# AddSub.net
KiCad netlist of a schematic drawn in EAGLE
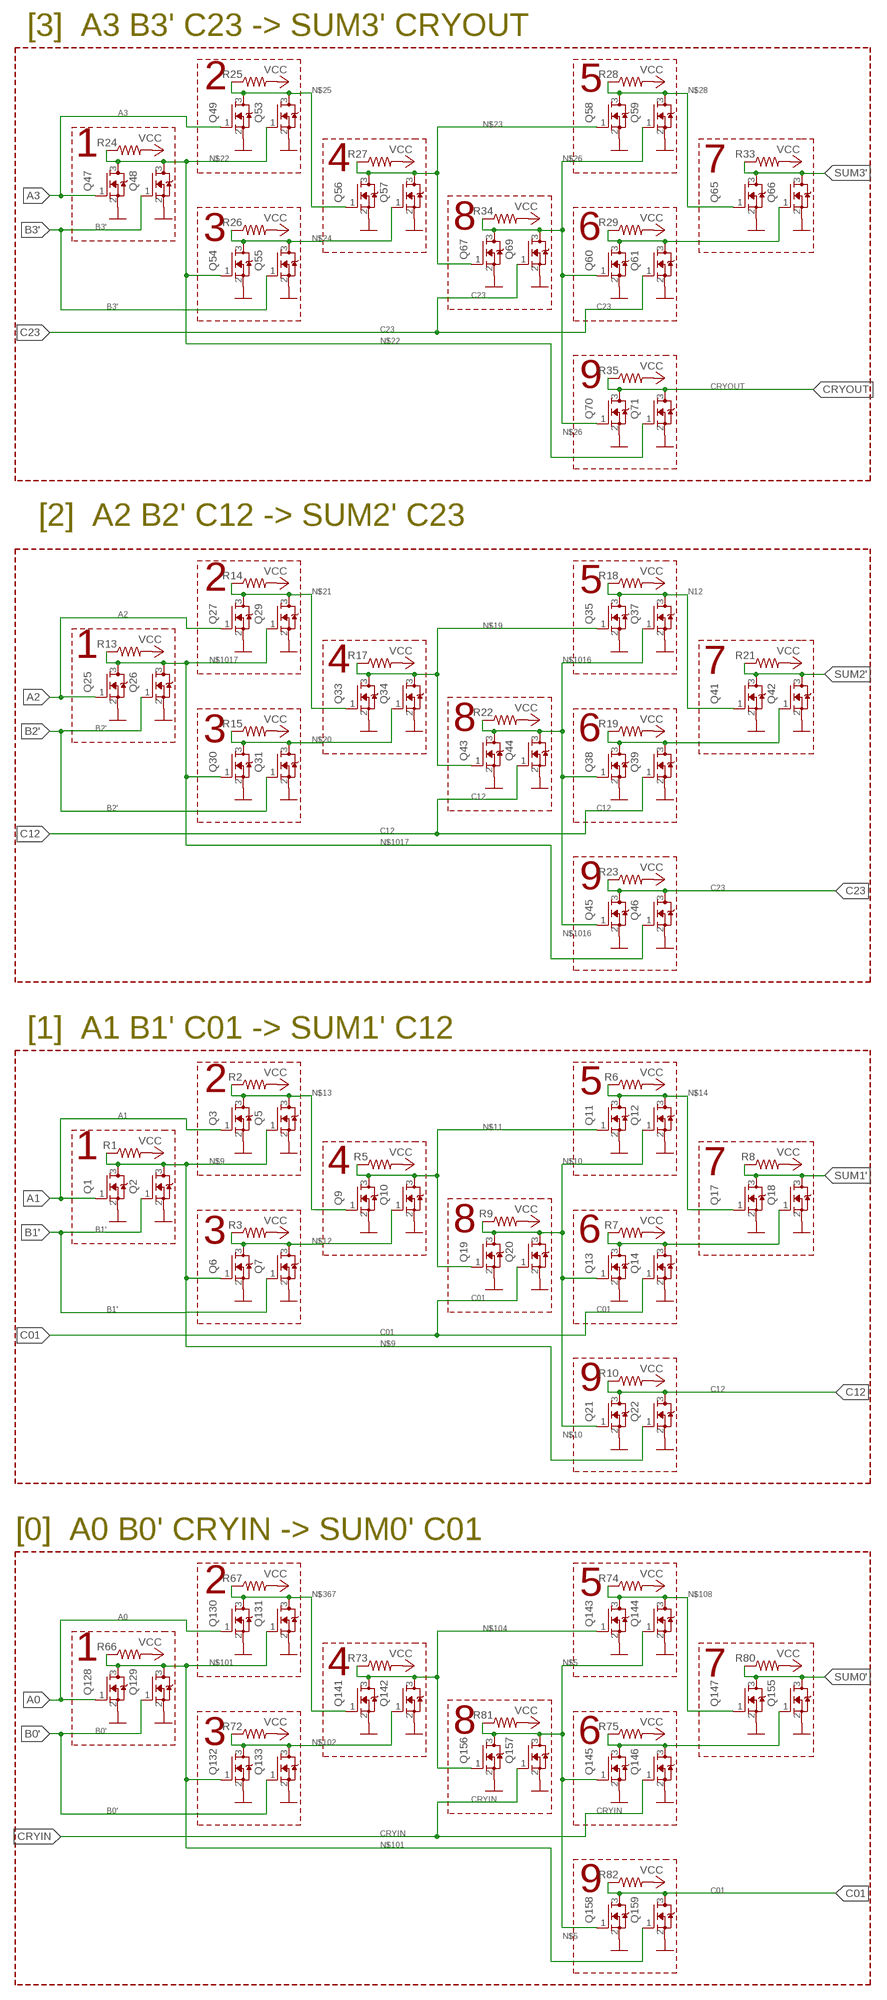
[diagram p0: schematic, sheet 1, part 1 of 2]
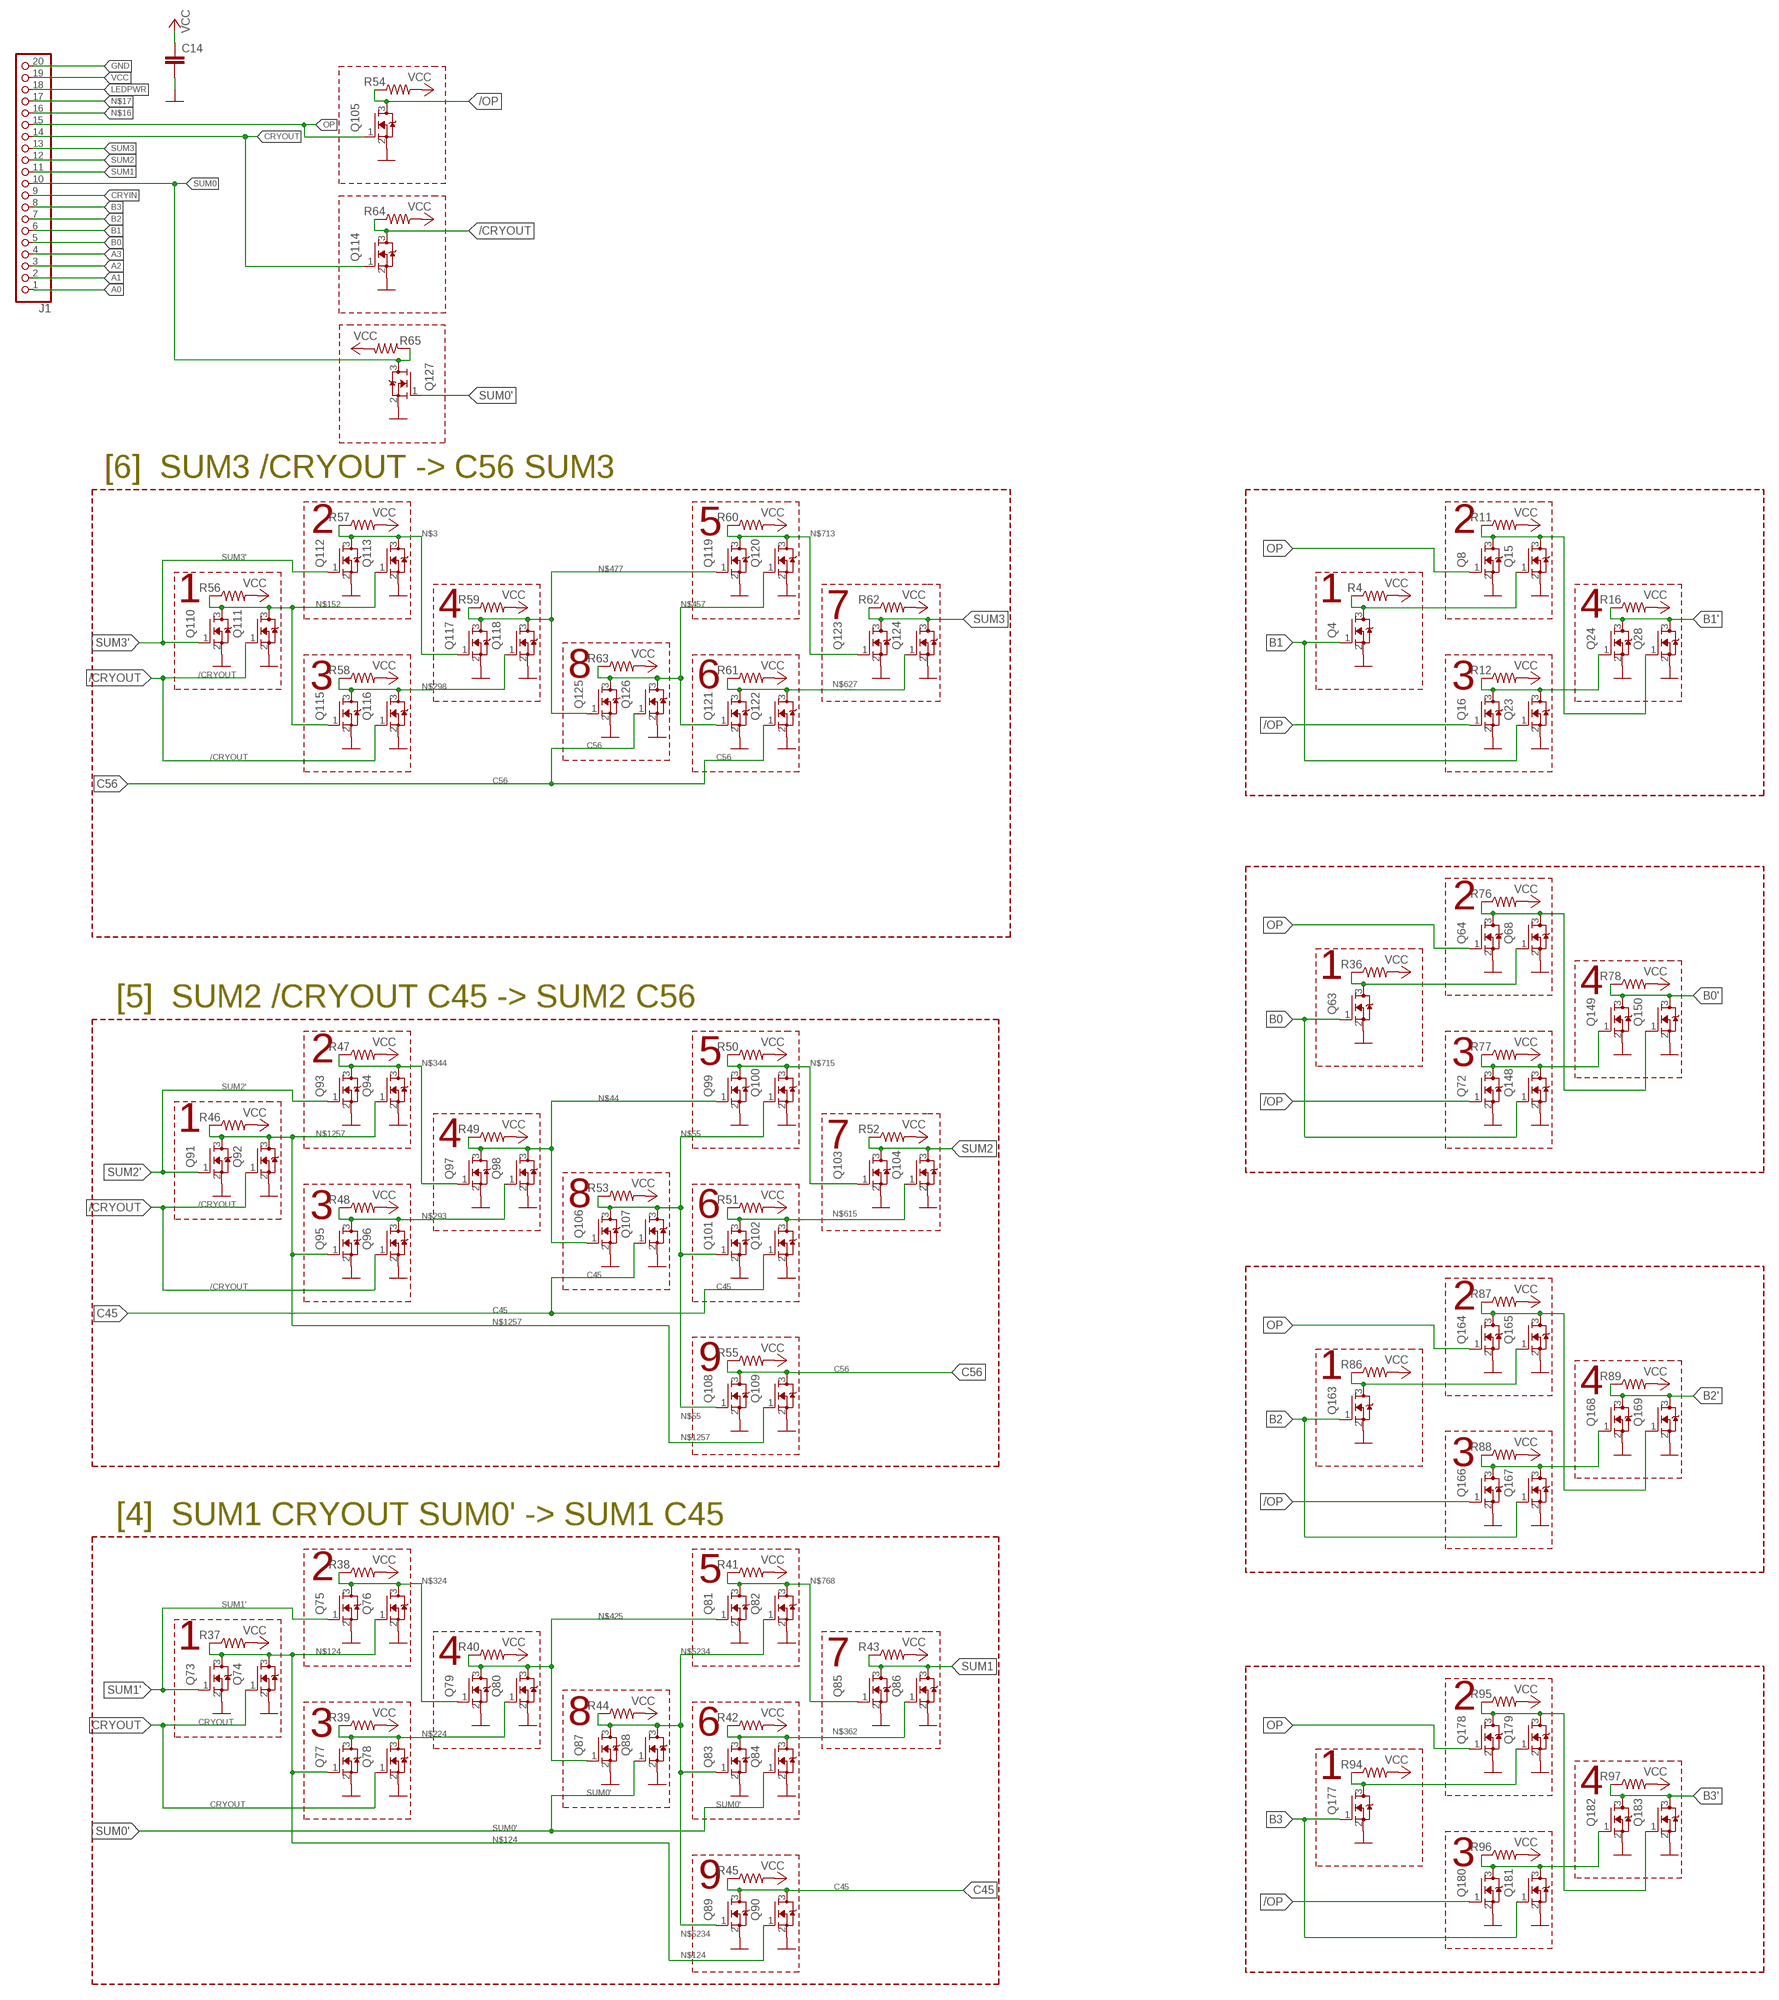
[diagram p1: schematic, sheet 1, part 2 of 2]

(export (version "E")
  (design (tool "Eeschema 10.0.6"))
  (components
    (comp (ref "C14")
      (value "C-EUC0805")
      (footprint "eagle-import:C0805")
      (libsource (lib "eagle-import") (part "C-EUC0805"))
    )
    (comp (ref "J1")
      (value "PINHD-1X20/90")
      (footprint "eagle-import:1X20_90")
      (libsource (lib "eagle-import") (part "PINHD-1X20/90"))
    )
    (comp (ref "Q1")
      (value "310mA/60V/1.6Ω")
      (footprint "eagle-import:SOT23")
      (libsource (lib "eagle-import") (part "NMOSREFLOW"))
    )
    (comp (ref "Q2")
      (value "310mA/60V/1.6Ω")
      (footprint "eagle-import:SOT23")
      (libsource (lib "eagle-import") (part "NMOSREFLOW"))
    )
    (comp (ref "Q3")
      (value "310mA/60V/1.6Ω")
      (footprint "eagle-import:SOT23")
      (libsource (lib "eagle-import") (part "NMOSREFLOW"))
    )
    (comp (ref "Q4")
      (value "310mA/60V/1.6Ω")
      (footprint "eagle-import:SOT23")
      (libsource (lib "eagle-import") (part "NMOSREFLOW"))
    )
    (comp (ref "Q5")
      (value "310mA/60V/1.6Ω")
      (footprint "eagle-import:SOT23")
      (libsource (lib "eagle-import") (part "NMOSREFLOW"))
    )
    (comp (ref "Q6")
      (value "310mA/60V/1.6Ω")
      (footprint "eagle-import:SOT23")
      (libsource (lib "eagle-import") (part "NMOSREFLOW"))
    )
    (comp (ref "Q7")
      (value "310mA/60V/1.6Ω")
      (footprint "eagle-import:SOT23")
      (libsource (lib "eagle-import") (part "NMOSREFLOW"))
    )
    (comp (ref "Q8")
      (value "310mA/60V/1.6Ω")
      (footprint "eagle-import:SOT23")
      (libsource (lib "eagle-import") (part "NMOSREFLOW"))
    )
    (comp (ref "Q9")
      (value "310mA/60V/1.6Ω")
      (footprint "eagle-import:SOT23")
      (libsource (lib "eagle-import") (part "NMOSREFLOW"))
    )
    (comp (ref "Q10")
      (value "310mA/60V/1.6Ω")
      (footprint "eagle-import:SOT23")
      (libsource (lib "eagle-import") (part "NMOSREFLOW"))
    )
    (comp (ref "Q11")
      (value "310mA/60V/1.6Ω")
      (footprint "eagle-import:SOT23")
      (libsource (lib "eagle-import") (part "NMOSREFLOW"))
    )
    (comp (ref "Q12")
      (value "310mA/60V/1.6Ω")
      (footprint "eagle-import:SOT23")
      (libsource (lib "eagle-import") (part "NMOSREFLOW"))
    )
    (comp (ref "Q13")
      (value "310mA/60V/1.6Ω")
      (footprint "eagle-import:SOT23")
      (libsource (lib "eagle-import") (part "NMOSREFLOW"))
    )
    (comp (ref "Q14")
      (value "310mA/60V/1.6Ω")
      (footprint "eagle-import:SOT23")
      (libsource (lib "eagle-import") (part "NMOSREFLOW"))
    )
    (comp (ref "Q15")
      (value "310mA/60V/1.6Ω")
      (footprint "eagle-import:SOT23")
      (libsource (lib "eagle-import") (part "NMOSREFLOW"))
    )
    (comp (ref "Q16")
      (value "310mA/60V/1.6Ω")
      (footprint "eagle-import:SOT23")
      (libsource (lib "eagle-import") (part "NMOSREFLOW"))
    )
    (comp (ref "Q17")
      (value "310mA/60V/1.6Ω")
      (footprint "eagle-import:SOT23")
      (libsource (lib "eagle-import") (part "NMOSREFLOW"))
    )
    (comp (ref "Q18")
      (value "310mA/60V/1.6Ω")
      (footprint "eagle-import:SOT23")
      (libsource (lib "eagle-import") (part "NMOSREFLOW"))
    )
    (comp (ref "Q19")
      (value "310mA/60V/1.6Ω")
      (footprint "eagle-import:SOT23")
      (libsource (lib "eagle-import") (part "NMOSREFLOW"))
    )
    (comp (ref "Q20")
      (value "310mA/60V/1.6Ω")
      (footprint "eagle-import:SOT23")
      (libsource (lib "eagle-import") (part "NMOSREFLOW"))
    )
    (comp (ref "Q21")
      (value "310mA/60V/1.6Ω")
      (footprint "eagle-import:SOT23")
      (libsource (lib "eagle-import") (part "NMOSREFLOW"))
    )
    (comp (ref "Q22")
      (value "310mA/60V/1.6Ω")
      (footprint "eagle-import:SOT23")
      (libsource (lib "eagle-import") (part "NMOSREFLOW"))
    )
    (comp (ref "Q23")
      (value "310mA/60V/1.6Ω")
      (footprint "eagle-import:SOT23")
      (libsource (lib "eagle-import") (part "NMOSREFLOW"))
    )
    (comp (ref "Q24")
      (value "310mA/60V/1.6Ω")
      (footprint "eagle-import:SOT23")
      (libsource (lib "eagle-import") (part "NMOSREFLOW"))
    )
    (comp (ref "Q25")
      (value "310mA/60V/1.6Ω")
      (footprint "eagle-import:SOT23")
      (libsource (lib "eagle-import") (part "NMOSREFLOW"))
    )
    (comp (ref "Q26")
      (value "310mA/60V/1.6Ω")
      (footprint "eagle-import:SOT23")
      (libsource (lib "eagle-import") (part "NMOSREFLOW"))
    )
    (comp (ref "Q27")
      (value "310mA/60V/1.6Ω")
      (footprint "eagle-import:SOT23")
      (libsource (lib "eagle-import") (part "NMOSREFLOW"))
    )
    (comp (ref "Q28")
      (value "310mA/60V/1.6Ω")
      (footprint "eagle-import:SOT23")
      (libsource (lib "eagle-import") (part "NMOSREFLOW"))
    )
    (comp (ref "Q29")
      (value "310mA/60V/1.6Ω")
      (footprint "eagle-import:SOT23")
      (libsource (lib "eagle-import") (part "NMOSREFLOW"))
    )
    (comp (ref "Q30")
      (value "310mA/60V/1.6Ω")
      (footprint "eagle-import:SOT23")
      (libsource (lib "eagle-import") (part "NMOSREFLOW"))
    )
    (comp (ref "Q31")
      (value "310mA/60V/1.6Ω")
      (footprint "eagle-import:SOT23")
      (libsource (lib "eagle-import") (part "NMOSREFLOW"))
    )
    (comp (ref "Q33")
      (value "310mA/60V/1.6Ω")
      (footprint "eagle-import:SOT23")
      (libsource (lib "eagle-import") (part "NMOSREFLOW"))
    )
    (comp (ref "Q34")
      (value "310mA/60V/1.6Ω")
      (footprint "eagle-import:SOT23")
      (libsource (lib "eagle-import") (part "NMOSREFLOW"))
    )
    (comp (ref "Q35")
      (value "310mA/60V/1.6Ω")
      (footprint "eagle-import:SOT23")
      (libsource (lib "eagle-import") (part "NMOSREFLOW"))
    )
    (comp (ref "Q37")
      (value "310mA/60V/1.6Ω")
      (footprint "eagle-import:SOT23")
      (libsource (lib "eagle-import") (part "NMOSREFLOW"))
    )
    (comp (ref "Q38")
      (value "310mA/60V/1.6Ω")
      (footprint "eagle-import:SOT23")
      (libsource (lib "eagle-import") (part "NMOSREFLOW"))
    )
    (comp (ref "Q39")
      (value "310mA/60V/1.6Ω")
      (footprint "eagle-import:SOT23")
      (libsource (lib "eagle-import") (part "NMOSREFLOW"))
    )
    (comp (ref "Q41")
      (value "310mA/60V/1.6Ω")
      (footprint "eagle-import:SOT23")
      (libsource (lib "eagle-import") (part "NMOSREFLOW"))
    )
    (comp (ref "Q42")
      (value "310mA/60V/1.6Ω")
      (footprint "eagle-import:SOT23")
      (libsource (lib "eagle-import") (part "NMOSREFLOW"))
    )
    (comp (ref "Q43")
      (value "310mA/60V/1.6Ω")
      (footprint "eagle-import:SOT23")
      (libsource (lib "eagle-import") (part "NMOSREFLOW"))
    )
    (comp (ref "Q44")
      (value "310mA/60V/1.6Ω")
      (footprint "eagle-import:SOT23")
      (libsource (lib "eagle-import") (part "NMOSREFLOW"))
    )
    (comp (ref "Q45")
      (value "310mA/60V/1.6Ω")
      (footprint "eagle-import:SOT23")
      (libsource (lib "eagle-import") (part "NMOSREFLOW"))
    )
    (comp (ref "Q46")
      (value "310mA/60V/1.6Ω")
      (footprint "eagle-import:SOT23")
      (libsource (lib "eagle-import") (part "NMOSREFLOW"))
    )
    (comp (ref "Q47")
      (value "310mA/60V/1.6Ω")
      (footprint "eagle-import:SOT23")
      (libsource (lib "eagle-import") (part "NMOSREFLOW"))
    )
    (comp (ref "Q48")
      (value "310mA/60V/1.6Ω")
      (footprint "eagle-import:SOT23")
      (libsource (lib "eagle-import") (part "NMOSREFLOW"))
    )
    (comp (ref "Q49")
      (value "310mA/60V/1.6Ω")
      (footprint "eagle-import:SOT23")
      (libsource (lib "eagle-import") (part "NMOSREFLOW"))
    )
    (comp (ref "Q53")
      (value "310mA/60V/1.6Ω")
      (footprint "eagle-import:SOT23")
      (libsource (lib "eagle-import") (part "NMOSREFLOW"))
    )
    (comp (ref "Q54")
      (value "310mA/60V/1.6Ω")
      (footprint "eagle-import:SOT23")
      (libsource (lib "eagle-import") (part "NMOSREFLOW"))
    )
    (comp (ref "Q55")
      (value "310mA/60V/1.6Ω")
      (footprint "eagle-import:SOT23")
      (libsource (lib "eagle-import") (part "NMOSREFLOW"))
    )
    (comp (ref "Q56")
      (value "310mA/60V/1.6Ω")
      (footprint "eagle-import:SOT23")
      (libsource (lib "eagle-import") (part "NMOSREFLOW"))
    )
    (comp (ref "Q57")
      (value "310mA/60V/1.6Ω")
      (footprint "eagle-import:SOT23")
      (libsource (lib "eagle-import") (part "NMOSREFLOW"))
    )
    (comp (ref "Q58")
      (value "310mA/60V/1.6Ω")
      (footprint "eagle-import:SOT23")
      (libsource (lib "eagle-import") (part "NMOSREFLOW"))
    )
    (comp (ref "Q59")
      (value "310mA/60V/1.6Ω")
      (footprint "eagle-import:SOT23")
      (libsource (lib "eagle-import") (part "NMOSREFLOW"))
    )
    (comp (ref "Q60")
      (value "310mA/60V/1.6Ω")
      (footprint "eagle-import:SOT23")
      (libsource (lib "eagle-import") (part "NMOSREFLOW"))
    )
    (comp (ref "Q61")
      (value "310mA/60V/1.6Ω")
      (footprint "eagle-import:SOT23")
      (libsource (lib "eagle-import") (part "NMOSREFLOW"))
    )
    (comp (ref "Q63")
      (value "310mA/60V/1.6Ω")
      (footprint "eagle-import:SOT23")
      (libsource (lib "eagle-import") (part "NMOSREFLOW"))
    )
    (comp (ref "Q64")
      (value "310mA/60V/1.6Ω")
      (footprint "eagle-import:SOT23")
      (libsource (lib "eagle-import") (part "NMOSREFLOW"))
    )
    (comp (ref "Q65")
      (value "310mA/60V/1.6Ω")
      (footprint "eagle-import:SOT23")
      (libsource (lib "eagle-import") (part "NMOSREFLOW"))
    )
    (comp (ref "Q66")
      (value "310mA/60V/1.6Ω")
      (footprint "eagle-import:SOT23")
      (libsource (lib "eagle-import") (part "NMOSREFLOW"))
    )
    (comp (ref "Q67")
      (value "310mA/60V/1.6Ω")
      (footprint "eagle-import:SOT23")
      (libsource (lib "eagle-import") (part "NMOSREFLOW"))
    )
    (comp (ref "Q68")
      (value "310mA/60V/1.6Ω")
      (footprint "eagle-import:SOT23")
      (libsource (lib "eagle-import") (part "NMOSREFLOW"))
    )
    (comp (ref "Q69")
      (value "310mA/60V/1.6Ω")
      (footprint "eagle-import:SOT23")
      (libsource (lib "eagle-import") (part "NMOSREFLOW"))
    )
    (comp (ref "Q70")
      (value "310mA/60V/1.6Ω")
      (footprint "eagle-import:SOT23")
      (libsource (lib "eagle-import") (part "NMOSREFLOW"))
    )
    (comp (ref "Q71")
      (value "310mA/60V/1.6Ω")
      (footprint "eagle-import:SOT23")
      (libsource (lib "eagle-import") (part "NMOSREFLOW"))
    )
    (comp (ref "Q72")
      (value "310mA/60V/1.6Ω")
      (footprint "eagle-import:SOT23")
      (libsource (lib "eagle-import") (part "NMOSREFLOW"))
    )
    (comp (ref "Q73")
      (value "310mA/60V/1.6Ω")
      (footprint "eagle-import:SOT23")
      (libsource (lib "eagle-import") (part "NMOSREFLOW"))
    )
    (comp (ref "Q74")
      (value "310mA/60V/1.6Ω")
      (footprint "eagle-import:SOT23")
      (libsource (lib "eagle-import") (part "NMOSREFLOW"))
    )
    (comp (ref "Q75")
      (value "310mA/60V/1.6Ω")
      (footprint "eagle-import:SOT23")
      (libsource (lib "eagle-import") (part "NMOSREFLOW"))
    )
    (comp (ref "Q76")
      (value "310mA/60V/1.6Ω")
      (footprint "eagle-import:SOT23")
      (libsource (lib "eagle-import") (part "NMOSREFLOW"))
    )
    (comp (ref "Q77")
      (value "310mA/60V/1.6Ω")
      (footprint "eagle-import:SOT23")
      (libsource (lib "eagle-import") (part "NMOSREFLOW"))
    )
    (comp (ref "Q78")
      (value "310mA/60V/1.6Ω")
      (footprint "eagle-import:SOT23")
      (libsource (lib "eagle-import") (part "NMOSREFLOW"))
    )
    (comp (ref "Q79")
      (value "310mA/60V/1.6Ω")
      (footprint "eagle-import:SOT23")
      (libsource (lib "eagle-import") (part "NMOSREFLOW"))
    )
    (comp (ref "Q80")
      (value "310mA/60V/1.6Ω")
      (footprint "eagle-import:SOT23")
      (libsource (lib "eagle-import") (part "NMOSREFLOW"))
    )
    (comp (ref "Q81")
      (value "310mA/60V/1.6Ω")
      (footprint "eagle-import:SOT23")
      (libsource (lib "eagle-import") (part "NMOSREFLOW"))
    )
    (comp (ref "Q82")
      (value "310mA/60V/1.6Ω")
      (footprint "eagle-import:SOT23")
      (libsource (lib "eagle-import") (part "NMOSREFLOW"))
    )
    (comp (ref "Q83")
      (value "310mA/60V/1.6Ω")
      (footprint "eagle-import:SOT23")
      (libsource (lib "eagle-import") (part "NMOSREFLOW"))
    )
    (comp (ref "Q84")
      (value "310mA/60V/1.6Ω")
      (footprint "eagle-import:SOT23")
      (libsource (lib "eagle-import") (part "NMOSREFLOW"))
    )
    (comp (ref "Q85")
      (value "310mA/60V/1.6Ω")
      (footprint "eagle-import:SOT23")
      (libsource (lib "eagle-import") (part "NMOSREFLOW"))
    )
    (comp (ref "Q86")
      (value "310mA/60V/1.6Ω")
      (footprint "eagle-import:SOT23")
      (libsource (lib "eagle-import") (part "NMOSREFLOW"))
    )
    (comp (ref "Q87")
      (value "310mA/60V/1.6Ω")
      (footprint "eagle-import:SOT23")
      (libsource (lib "eagle-import") (part "NMOSREFLOW"))
    )
    (comp (ref "Q88")
      (value "310mA/60V/1.6Ω")
      (footprint "eagle-import:SOT23")
      (libsource (lib "eagle-import") (part "NMOSREFLOW"))
    )
    (comp (ref "Q89")
      (value "310mA/60V/1.6Ω")
      (footprint "eagle-import:SOT23")
      (libsource (lib "eagle-import") (part "NMOSREFLOW"))
    )
    (comp (ref "Q90")
      (value "310mA/60V/1.6Ω")
      (footprint "eagle-import:SOT23")
      (libsource (lib "eagle-import") (part "NMOSREFLOW"))
    )
    (comp (ref "Q91")
      (value "310mA/60V/1.6Ω")
      (footprint "eagle-import:SOT23")
      (libsource (lib "eagle-import") (part "NMOSREFLOW"))
    )
    (comp (ref "Q92")
      (value "310mA/60V/1.6Ω")
      (footprint "eagle-import:SOT23")
      (libsource (lib "eagle-import") (part "NMOSREFLOW"))
    )
    (comp (ref "Q93")
      (value "310mA/60V/1.6Ω")
      (footprint "eagle-import:SOT23")
      (libsource (lib "eagle-import") (part "NMOSREFLOW"))
    )
    (comp (ref "Q94")
      (value "310mA/60V/1.6Ω")
      (footprint "eagle-import:SOT23")
      (libsource (lib "eagle-import") (part "NMOSREFLOW"))
    )
    (comp (ref "Q95")
      (value "310mA/60V/1.6Ω")
      (footprint "eagle-import:SOT23")
      (libsource (lib "eagle-import") (part "NMOSREFLOW"))
    )
    (comp (ref "Q96")
      (value "310mA/60V/1.6Ω")
      (footprint "eagle-import:SOT23")
      (libsource (lib "eagle-import") (part "NMOSREFLOW"))
    )
    (comp (ref "Q97")
      (value "310mA/60V/1.6Ω")
      (footprint "eagle-import:SOT23")
      (libsource (lib "eagle-import") (part "NMOSREFLOW"))
    )
    (comp (ref "Q98")
      (value "310mA/60V/1.6Ω")
      (footprint "eagle-import:SOT23")
      (libsource (lib "eagle-import") (part "NMOSREFLOW"))
    )
    (comp (ref "Q99")
      (value "310mA/60V/1.6Ω")
      (footprint "eagle-import:SOT23")
      (libsource (lib "eagle-import") (part "NMOSREFLOW"))
    )
    (comp (ref "Q100")
      (value "310mA/60V/1.6Ω")
      (footprint "eagle-import:SOT23")
      (libsource (lib "eagle-import") (part "NMOSREFLOW"))
    )
    (comp (ref "Q101")
      (value "310mA/60V/1.6Ω")
      (footprint "eagle-import:SOT23")
      (libsource (lib "eagle-import") (part "NMOSREFLOW"))
    )
    (comp (ref "Q102")
      (value "310mA/60V/1.6Ω")
      (footprint "eagle-import:SOT23")
      (libsource (lib "eagle-import") (part "NMOSREFLOW"))
    )
    (comp (ref "Q103")
      (value "310mA/60V/1.6Ω")
      (footprint "eagle-import:SOT23")
      (libsource (lib "eagle-import") (part "NMOSREFLOW"))
    )
    (comp (ref "Q104")
      (value "310mA/60V/1.6Ω")
      (footprint "eagle-import:SOT23")
      (libsource (lib "eagle-import") (part "NMOSREFLOW"))
    )
    (comp (ref "Q105")
      (value "310mA/60V/1.6Ω")
      (footprint "eagle-import:SOT23")
      (libsource (lib "eagle-import") (part "NMOSREFLOW"))
    )
    (comp (ref "Q106")
      (value "310mA/60V/1.6Ω")
      (footprint "eagle-import:SOT23")
      (libsource (lib "eagle-import") (part "NMOSREFLOW"))
    )
    (comp (ref "Q107")
      (value "310mA/60V/1.6Ω")
      (footprint "eagle-import:SOT23")
      (libsource (lib "eagle-import") (part "NMOSREFLOW"))
    )
    (comp (ref "Q108")
      (value "310mA/60V/1.6Ω")
      (footprint "eagle-import:SOT23")
      (libsource (lib "eagle-import") (part "NMOSREFLOW"))
    )
    (comp (ref "Q109")
      (value "310mA/60V/1.6Ω")
      (footprint "eagle-import:SOT23")
      (libsource (lib "eagle-import") (part "NMOSREFLOW"))
    )
    (comp (ref "Q110")
      (value "310mA/60V/1.6Ω")
      (footprint "eagle-import:SOT23")
      (libsource (lib "eagle-import") (part "NMOSREFLOW"))
    )
    (comp (ref "Q111")
      (value "310mA/60V/1.6Ω")
      (footprint "eagle-import:SOT23")
      (libsource (lib "eagle-import") (part "NMOSREFLOW"))
    )
    (comp (ref "Q112")
      (value "310mA/60V/1.6Ω")
      (footprint "eagle-import:SOT23")
      (libsource (lib "eagle-import") (part "NMOSREFLOW"))
    )
    (comp (ref "Q113")
      (value "310mA/60V/1.6Ω")
      (footprint "eagle-import:SOT23")
      (libsource (lib "eagle-import") (part "NMOSREFLOW"))
    )
    (comp (ref "Q114")
      (value "310mA/60V/1.6Ω")
      (footprint "eagle-import:SOT23")
      (libsource (lib "eagle-import") (part "NMOSREFLOW"))
    )
    (comp (ref "Q115")
      (value "310mA/60V/1.6Ω")
      (footprint "eagle-import:SOT23")
      (libsource (lib "eagle-import") (part "NMOSREFLOW"))
    )
    (comp (ref "Q116")
      (value "310mA/60V/1.6Ω")
      (footprint "eagle-import:SOT23")
      (libsource (lib "eagle-import") (part "NMOSREFLOW"))
    )
    (comp (ref "Q117")
      (value "310mA/60V/1.6Ω")
      (footprint "eagle-import:SOT23")
      (libsource (lib "eagle-import") (part "NMOSREFLOW"))
    )
    (comp (ref "Q118")
      (value "310mA/60V/1.6Ω")
      (footprint "eagle-import:SOT23")
      (libsource (lib "eagle-import") (part "NMOSREFLOW"))
    )
    (comp (ref "Q119")
      (value "310mA/60V/1.6Ω")
      (footprint "eagle-import:SOT23")
      (libsource (lib "eagle-import") (part "NMOSREFLOW"))
    )
    (comp (ref "Q120")
      (value "310mA/60V/1.6Ω")
      (footprint "eagle-import:SOT23")
      (libsource (lib "eagle-import") (part "NMOSREFLOW"))
    )
    (comp (ref "Q121")
      (value "310mA/60V/1.6Ω")
      (footprint "eagle-import:SOT23")
      (libsource (lib "eagle-import") (part "NMOSREFLOW"))
    )
    (comp (ref "Q122")
      (value "310mA/60V/1.6Ω")
      (footprint "eagle-import:SOT23")
      (libsource (lib "eagle-import") (part "NMOSREFLOW"))
    )
    (comp (ref "Q123")
      (value "310mA/60V/1.6Ω")
      (footprint "eagle-import:SOT23")
      (libsource (lib "eagle-import") (part "NMOSREFLOW"))
    )
    (comp (ref "Q124")
      (value "310mA/60V/1.6Ω")
      (footprint "eagle-import:SOT23")
      (libsource (lib "eagle-import") (part "NMOSREFLOW"))
    )
    (comp (ref "Q125")
      (value "310mA/60V/1.6Ω")
      (footprint "eagle-import:SOT23")
      (libsource (lib "eagle-import") (part "NMOSREFLOW"))
    )
    (comp (ref "Q126")
      (value "310mA/60V/1.6Ω")
      (footprint "eagle-import:SOT23")
      (libsource (lib "eagle-import") (part "NMOSREFLOW"))
    )
    (comp (ref "Q127")
      (value "310mA/60V/1.6Ω")
      (footprint "eagle-import:SOT23")
      (libsource (lib "eagle-import") (part "NMOSREFLOW"))
    )
    (comp (ref "Q128")
      (value "310mA/60V/1.6Ω")
      (footprint "eagle-import:SOT23")
      (libsource (lib "eagle-import") (part "NMOSREFLOW"))
    )
    (comp (ref "Q129")
      (value "310mA/60V/1.6Ω")
      (footprint "eagle-import:SOT23")
      (libsource (lib "eagle-import") (part "NMOSREFLOW"))
    )
    (comp (ref "Q130")
      (value "310mA/60V/1.6Ω")
      (footprint "eagle-import:SOT23")
      (libsource (lib "eagle-import") (part "NMOSREFLOW"))
    )
    (comp (ref "Q131")
      (value "310mA/60V/1.6Ω")
      (footprint "eagle-import:SOT23")
      (libsource (lib "eagle-import") (part "NMOSREFLOW"))
    )
    (comp (ref "Q132")
      (value "310mA/60V/1.6Ω")
      (footprint "eagle-import:SOT23")
      (libsource (lib "eagle-import") (part "NMOSREFLOW"))
    )
    (comp (ref "Q133")
      (value "310mA/60V/1.6Ω")
      (footprint "eagle-import:SOT23")
      (libsource (lib "eagle-import") (part "NMOSREFLOW"))
    )
    (comp (ref "Q141")
      (value "310mA/60V/1.6Ω")
      (footprint "eagle-import:SOT23")
      (libsource (lib "eagle-import") (part "NMOSREFLOW"))
    )
    (comp (ref "Q142")
      (value "310mA/60V/1.6Ω")
      (footprint "eagle-import:SOT23")
      (libsource (lib "eagle-import") (part "NMOSREFLOW"))
    )
    (comp (ref "Q143")
      (value "310mA/60V/1.6Ω")
      (footprint "eagle-import:SOT23")
      (libsource (lib "eagle-import") (part "NMOSREFLOW"))
    )
    (comp (ref "Q144")
      (value "310mA/60V/1.6Ω")
      (footprint "eagle-import:SOT23")
      (libsource (lib "eagle-import") (part "NMOSREFLOW"))
    )
    (comp (ref "Q145")
      (value "310mA/60V/1.6Ω")
      (footprint "eagle-import:SOT23")
      (libsource (lib "eagle-import") (part "NMOSREFLOW"))
    )
    (comp (ref "Q146")
      (value "310mA/60V/1.6Ω")
      (footprint "eagle-import:SOT23")
      (libsource (lib "eagle-import") (part "NMOSREFLOW"))
    )
    (comp (ref "Q147")
      (value "310mA/60V/1.6Ω")
      (footprint "eagle-import:SOT23")
      (libsource (lib "eagle-import") (part "NMOSREFLOW"))
    )
    (comp (ref "Q148")
      (value "310mA/60V/1.6Ω")
      (footprint "eagle-import:SOT23")
      (libsource (lib "eagle-import") (part "NMOSREFLOW"))
    )
    (comp (ref "Q149")
      (value "310mA/60V/1.6Ω")
      (footprint "eagle-import:SOT23")
      (libsource (lib "eagle-import") (part "NMOSREFLOW"))
    )
    (comp (ref "Q150")
      (value "310mA/60V/1.6Ω")
      (footprint "eagle-import:SOT23")
      (libsource (lib "eagle-import") (part "NMOSREFLOW"))
    )
    (comp (ref "Q155")
      (value "310mA/60V/1.6Ω")
      (footprint "eagle-import:SOT23")
      (libsource (lib "eagle-import") (part "NMOSREFLOW"))
    )
    (comp (ref "Q156")
      (value "310mA/60V/1.6Ω")
      (footprint "eagle-import:SOT23")
      (libsource (lib "eagle-import") (part "NMOSREFLOW"))
    )
    (comp (ref "Q157")
      (value "310mA/60V/1.6Ω")
      (footprint "eagle-import:SOT23")
      (libsource (lib "eagle-import") (part "NMOSREFLOW"))
    )
    (comp (ref "Q158")
      (value "310mA/60V/1.6Ω")
      (footprint "eagle-import:SOT23")
      (libsource (lib "eagle-import") (part "NMOSREFLOW"))
    )
    (comp (ref "Q159")
      (value "310mA/60V/1.6Ω")
      (footprint "eagle-import:SOT23")
      (libsource (lib "eagle-import") (part "NMOSREFLOW"))
    )
    (comp (ref "Q163")
      (value "310mA/60V/1.6Ω")
      (footprint "eagle-import:SOT23")
      (libsource (lib "eagle-import") (part "NMOSREFLOW"))
    )
    (comp (ref "Q164")
      (value "310mA/60V/1.6Ω")
      (footprint "eagle-import:SOT23")
      (libsource (lib "eagle-import") (part "NMOSREFLOW"))
    )
    (comp (ref "Q165")
      (value "310mA/60V/1.6Ω")
      (footprint "eagle-import:SOT23")
      (libsource (lib "eagle-import") (part "NMOSREFLOW"))
    )
    (comp (ref "Q166")
      (value "310mA/60V/1.6Ω")
      (footprint "eagle-import:SOT23")
      (libsource (lib "eagle-import") (part "NMOSREFLOW"))
    )
    (comp (ref "Q167")
      (value "310mA/60V/1.6Ω")
      (footprint "eagle-import:SOT23")
      (libsource (lib "eagle-import") (part "NMOSREFLOW"))
    )
    (comp (ref "Q168")
      (value "310mA/60V/1.6Ω")
      (footprint "eagle-import:SOT23")
      (libsource (lib "eagle-import") (part "NMOSREFLOW"))
    )
    (comp (ref "Q169")
      (value "310mA/60V/1.6Ω")
      (footprint "eagle-import:SOT23")
      (libsource (lib "eagle-import") (part "NMOSREFLOW"))
    )
    (comp (ref "Q177")
      (value "310mA/60V/1.6Ω")
      (footprint "eagle-import:SOT23")
      (libsource (lib "eagle-import") (part "NMOSREFLOW"))
    )
    (comp (ref "Q178")
      (value "310mA/60V/1.6Ω")
      (footprint "eagle-import:SOT23")
      (libsource (lib "eagle-import") (part "NMOSREFLOW"))
    )
    (comp (ref "Q179")
      (value "310mA/60V/1.6Ω")
      (footprint "eagle-import:SOT23")
      (libsource (lib "eagle-import") (part "NMOSREFLOW"))
    )
    (comp (ref "Q180")
      (value "310mA/60V/1.6Ω")
      (footprint "eagle-import:SOT23")
      (libsource (lib "eagle-import") (part "NMOSREFLOW"))
    )
    (comp (ref "Q181")
      (value "310mA/60V/1.6Ω")
      (footprint "eagle-import:SOT23")
      (libsource (lib "eagle-import") (part "NMOSREFLOW"))
    )
    (comp (ref "Q182")
      (value "310mA/60V/1.6Ω")
      (footprint "eagle-import:SOT23")
      (libsource (lib "eagle-import") (part "NMOSREFLOW"))
    )
    (comp (ref "Q183")
      (value "310mA/60V/1.6Ω")
      (footprint "eagle-import:SOT23")
      (libsource (lib "eagle-import") (part "NMOSREFLOW"))
    )
    (comp (ref "R1")
      (value "RESISTOR0805")
      (footprint "eagle-import:0805")
      (libsource (lib "eagle-import") (part "RESISTOR0805"))
    )
    (comp (ref "R2")
      (value "RESISTOR0805")
      (footprint "eagle-import:0805")
      (libsource (lib "eagle-import") (part "RESISTOR0805"))
    )
    (comp (ref "R3")
      (value "RESISTOR0805")
      (footprint "eagle-import:0805")
      (libsource (lib "eagle-import") (part "RESISTOR0805"))
    )
    (comp (ref "R4")
      (value "RESISTOR0805")
      (footprint "eagle-import:0805")
      (libsource (lib "eagle-import") (part "RESISTOR0805"))
    )
    (comp (ref "R5")
      (value "RESISTOR0805")
      (footprint "eagle-import:0805")
      (libsource (lib "eagle-import") (part "RESISTOR0805"))
    )
    (comp (ref "R6")
      (value "RESISTOR0805")
      (footprint "eagle-import:0805")
      (libsource (lib "eagle-import") (part "RESISTOR0805"))
    )
    (comp (ref "R7")
      (value "RESISTOR0805")
      (footprint "eagle-import:0805")
      (libsource (lib "eagle-import") (part "RESISTOR0805"))
    )
    (comp (ref "R8")
      (value "RESISTOR0805")
      (footprint "eagle-import:0805")
      (libsource (lib "eagle-import") (part "RESISTOR0805"))
    )
    (comp (ref "R9")
      (value "RESISTOR0805")
      (footprint "eagle-import:0805")
      (libsource (lib "eagle-import") (part "RESISTOR0805"))
    )
    (comp (ref "R10")
      (value "RESISTOR0805")
      (footprint "eagle-import:0805")
      (libsource (lib "eagle-import") (part "RESISTOR0805"))
    )
    (comp (ref "R11")
      (value "RESISTOR0805")
      (footprint "eagle-import:0805")
      (libsource (lib "eagle-import") (part "RESISTOR0805"))
    )
    (comp (ref "R12")
      (value "RESISTOR0805")
      (footprint "eagle-import:0805")
      (libsource (lib "eagle-import") (part "RESISTOR0805"))
    )
    (comp (ref "R13")
      (value "RESISTOR0805")
      (footprint "eagle-import:0805")
      (libsource (lib "eagle-import") (part "RESISTOR0805"))
    )
    (comp (ref "R14")
      (value "RESISTOR0805")
      (footprint "eagle-import:0805")
      (libsource (lib "eagle-import") (part "RESISTOR0805"))
    )
    (comp (ref "R15")
      (value "RESISTOR0805")
      (footprint "eagle-import:0805")
      (libsource (lib "eagle-import") (part "RESISTOR0805"))
    )
    (comp (ref "R16")
      (value "RESISTOR0805")
      (footprint "eagle-import:0805")
      (libsource (lib "eagle-import") (part "RESISTOR0805"))
    )
    (comp (ref "R17")
      (value "RESISTOR0805")
      (footprint "eagle-import:0805")
      (libsource (lib "eagle-import") (part "RESISTOR0805"))
    )
    (comp (ref "R18")
      (value "RESISTOR0805")
      (footprint "eagle-import:0805")
      (libsource (lib "eagle-import") (part "RESISTOR0805"))
    )
    (comp (ref "R19")
      (value "RESISTOR0805")
      (footprint "eagle-import:0805")
      (libsource (lib "eagle-import") (part "RESISTOR0805"))
    )
    (comp (ref "R21")
      (value "RESISTOR0805")
      (footprint "eagle-import:0805")
      (libsource (lib "eagle-import") (part "RESISTOR0805"))
    )
    (comp (ref "R22")
      (value "RESISTOR0805")
      (footprint "eagle-import:0805")
      (libsource (lib "eagle-import") (part "RESISTOR0805"))
    )
    (comp (ref "R23")
      (value "RESISTOR0805")
      (footprint "eagle-import:0805")
      (libsource (lib "eagle-import") (part "RESISTOR0805"))
    )
    (comp (ref "R24")
      (value "RESISTOR0805")
      (footprint "eagle-import:0805")
      (libsource (lib "eagle-import") (part "RESISTOR0805"))
    )
    (comp (ref "R25")
      (value "RESISTOR0805")
      (footprint "eagle-import:0805")
      (libsource (lib "eagle-import") (part "RESISTOR0805"))
    )
    (comp (ref "R26")
      (value "RESISTOR0805")
      (footprint "eagle-import:0805")
      (libsource (lib "eagle-import") (part "RESISTOR0805"))
    )
    (comp (ref "R27")
      (value "RESISTOR0805")
      (footprint "eagle-import:0805")
      (libsource (lib "eagle-import") (part "RESISTOR0805"))
    )
    (comp (ref "R28")
      (value "RESISTOR0805")
      (footprint "eagle-import:0805")
      (libsource (lib "eagle-import") (part "RESISTOR0805"))
    )
    (comp (ref "R29")
      (value "RESISTOR0805")
      (footprint "eagle-import:0805")
      (libsource (lib "eagle-import") (part "RESISTOR0805"))
    )
    (comp (ref "R33")
      (value "RESISTOR0805")
      (footprint "eagle-import:0805")
      (libsource (lib "eagle-import") (part "RESISTOR0805"))
    )
    (comp (ref "R34")
      (value "RESISTOR0805")
      (footprint "eagle-import:0805")
      (libsource (lib "eagle-import") (part "RESISTOR0805"))
    )
    (comp (ref "R35")
      (value "RESISTOR0805")
      (footprint "eagle-import:0805")
      (libsource (lib "eagle-import") (part "RESISTOR0805"))
    )
    (comp (ref "R36")
      (value "RESISTOR0805")
      (footprint "eagle-import:0805")
      (libsource (lib "eagle-import") (part "RESISTOR0805"))
    )
    (comp (ref "R37")
      (value "RESISTOR0805")
      (footprint "eagle-import:0805")
      (libsource (lib "eagle-import") (part "RESISTOR0805"))
    )
    (comp (ref "R38")
      (value "RESISTOR0805")
      (footprint "eagle-import:0805")
      (libsource (lib "eagle-import") (part "RESISTOR0805"))
    )
    (comp (ref "R39")
      (value "RESISTOR0805")
      (footprint "eagle-import:0805")
      (libsource (lib "eagle-import") (part "RESISTOR0805"))
    )
    (comp (ref "R40")
      (value "RESISTOR0805")
      (footprint "eagle-import:0805")
      (libsource (lib "eagle-import") (part "RESISTOR0805"))
    )
    (comp (ref "R41")
      (value "RESISTOR0805")
      (footprint "eagle-import:0805")
      (libsource (lib "eagle-import") (part "RESISTOR0805"))
    )
    (comp (ref "R42")
      (value "RESISTOR0805")
      (footprint "eagle-import:0805")
      (libsource (lib "eagle-import") (part "RESISTOR0805"))
    )
    (comp (ref "R43")
      (value "RESISTOR0805")
      (footprint "eagle-import:0805")
      (libsource (lib "eagle-import") (part "RESISTOR0805"))
    )
    (comp (ref "R44")
      (value "RESISTOR0805")
      (footprint "eagle-import:0805")
      (libsource (lib "eagle-import") (part "RESISTOR0805"))
    )
    (comp (ref "R45")
      (value "RESISTOR0805")
      (footprint "eagle-import:0805")
      (libsource (lib "eagle-import") (part "RESISTOR0805"))
    )
    (comp (ref "R46")
      (value "RESISTOR0805")
      (footprint "eagle-import:0805")
      (libsource (lib "eagle-import") (part "RESISTOR0805"))
    )
    (comp (ref "R47")
      (value "RESISTOR0805")
      (footprint "eagle-import:0805")
      (libsource (lib "eagle-import") (part "RESISTOR0805"))
    )
    (comp (ref "R48")
      (value "RESISTOR0805")
      (footprint "eagle-import:0805")
      (libsource (lib "eagle-import") (part "RESISTOR0805"))
    )
    (comp (ref "R49")
      (value "RESISTOR0805")
      (footprint "eagle-import:0805")
      (libsource (lib "eagle-import") (part "RESISTOR0805"))
    )
    (comp (ref "R50")
      (value "RESISTOR0805")
      (footprint "eagle-import:0805")
      (libsource (lib "eagle-import") (part "RESISTOR0805"))
    )
    (comp (ref "R51")
      (value "RESISTOR0805")
      (footprint "eagle-import:0805")
      (libsource (lib "eagle-import") (part "RESISTOR0805"))
    )
    (comp (ref "R52")
      (value "RESISTOR0805")
      (footprint "eagle-import:0805")
      (libsource (lib "eagle-import") (part "RESISTOR0805"))
    )
    (comp (ref "R53")
      (value "RESISTOR0805")
      (footprint "eagle-import:0805")
      (libsource (lib "eagle-import") (part "RESISTOR0805"))
    )
    (comp (ref "R54")
      (value "RESISTOR0805")
      (footprint "eagle-import:0805")
      (libsource (lib "eagle-import") (part "RESISTOR0805"))
    )
    (comp (ref "R55")
      (value "RESISTOR0805")
      (footprint "eagle-import:0805")
      (libsource (lib "eagle-import") (part "RESISTOR0805"))
    )
    (comp (ref "R56")
      (value "RESISTOR0805")
      (footprint "eagle-import:0805")
      (libsource (lib "eagle-import") (part "RESISTOR0805"))
    )
    (comp (ref "R57")
      (value "RESISTOR0805")
      (footprint "eagle-import:0805")
      (libsource (lib "eagle-import") (part "RESISTOR0805"))
    )
    (comp (ref "R58")
      (value "RESISTOR0805")
      (footprint "eagle-import:0805")
      (libsource (lib "eagle-import") (part "RESISTOR0805"))
    )
    (comp (ref "R59")
      (value "RESISTOR0805")
      (footprint "eagle-import:0805")
      (libsource (lib "eagle-import") (part "RESISTOR0805"))
    )
    (comp (ref "R60")
      (value "RESISTOR0805")
      (footprint "eagle-import:0805")
      (libsource (lib "eagle-import") (part "RESISTOR0805"))
    )
    (comp (ref "R61")
      (value "RESISTOR0805")
      (footprint "eagle-import:0805")
      (libsource (lib "eagle-import") (part "RESISTOR0805"))
    )
    (comp (ref "R62")
      (value "RESISTOR0805")
      (footprint "eagle-import:0805")
      (libsource (lib "eagle-import") (part "RESISTOR0805"))
    )
    (comp (ref "R63")
      (value "RESISTOR0805")
      (footprint "eagle-import:0805")
      (libsource (lib "eagle-import") (part "RESISTOR0805"))
    )
    (comp (ref "R64")
      (value "RESISTOR0805")
      (footprint "eagle-import:0805")
      (libsource (lib "eagle-import") (part "RESISTOR0805"))
    )
    (comp (ref "R65")
      (value "RESISTOR0805")
      (footprint "eagle-import:0805")
      (libsource (lib "eagle-import") (part "RESISTOR0805"))
    )
    (comp (ref "R66")
      (value "RESISTOR0805")
      (footprint "eagle-import:0805")
      (libsource (lib "eagle-import") (part "RESISTOR0805"))
    )
    (comp (ref "R67")
      (value "RESISTOR0805")
      (footprint "eagle-import:0805")
      (libsource (lib "eagle-import") (part "RESISTOR0805"))
    )
    (comp (ref "R72")
      (value "RESISTOR0805")
      (footprint "eagle-import:0805")
      (libsource (lib "eagle-import") (part "RESISTOR0805"))
    )
    (comp (ref "R73")
      (value "RESISTOR0805")
      (footprint "eagle-import:0805")
      (libsource (lib "eagle-import") (part "RESISTOR0805"))
    )
    (comp (ref "R74")
      (value "RESISTOR0805")
      (footprint "eagle-import:0805")
      (libsource (lib "eagle-import") (part "RESISTOR0805"))
    )
    (comp (ref "R75")
      (value "RESISTOR0805")
      (footprint "eagle-import:0805")
      (libsource (lib "eagle-import") (part "RESISTOR0805"))
    )
    (comp (ref "R76")
      (value "RESISTOR0805")
      (footprint "eagle-import:0805")
      (libsource (lib "eagle-import") (part "RESISTOR0805"))
    )
    (comp (ref "R77")
      (value "RESISTOR0805")
      (footprint "eagle-import:0805")
      (libsource (lib "eagle-import") (part "RESISTOR0805"))
    )
    (comp (ref "R78")
      (value "RESISTOR0805")
      (footprint "eagle-import:0805")
      (libsource (lib "eagle-import") (part "RESISTOR0805"))
    )
    (comp (ref "R80")
      (value "RESISTOR0805")
      (footprint "eagle-import:0805")
      (libsource (lib "eagle-import") (part "RESISTOR0805"))
    )
    (comp (ref "R81")
      (value "RESISTOR0805")
      (footprint "eagle-import:0805")
      (libsource (lib "eagle-import") (part "RESISTOR0805"))
    )
    (comp (ref "R82")
      (value "RESISTOR0805")
      (footprint "eagle-import:0805")
      (libsource (lib "eagle-import") (part "RESISTOR0805"))
    )
    (comp (ref "R86")
      (value "RESISTOR0805")
      (footprint "eagle-import:0805")
      (libsource (lib "eagle-import") (part "RESISTOR0805"))
    )
    (comp (ref "R87")
      (value "RESISTOR0805")
      (footprint "eagle-import:0805")
      (libsource (lib "eagle-import") (part "RESISTOR0805"))
    )
    (comp (ref "R88")
      (value "RESISTOR0805")
      (footprint "eagle-import:0805")
      (libsource (lib "eagle-import") (part "RESISTOR0805"))
    )
    (comp (ref "R89")
      (value "RESISTOR0805")
      (footprint "eagle-import:0805")
      (libsource (lib "eagle-import") (part "RESISTOR0805"))
    )
    (comp (ref "R94")
      (value "RESISTOR0805")
      (footprint "eagle-import:0805")
      (libsource (lib "eagle-import") (part "RESISTOR0805"))
    )
    (comp (ref "R95")
      (value "RESISTOR0805")
      (footprint "eagle-import:0805")
      (libsource (lib "eagle-import") (part "RESISTOR0805"))
    )
    (comp (ref "R96")
      (value "RESISTOR0805")
      (footprint "eagle-import:0805")
      (libsource (lib "eagle-import") (part "RESISTOR0805"))
    )
    (comp (ref "R97")
      (value "RESISTOR0805")
      (footprint "eagle-import:0805")
      (libsource (lib "eagle-import") (part "RESISTOR0805"))
    )
  )
  (nets
    (net (code "1") (name "/N$3") (class "Default")
      (node (ref "Q112") (pin "3") (pinfunction "D_3") (pintype "bidirectional"))
      (node (ref "Q113") (pin "3") (pinfunction "D_3") (pintype "bidirectional"))
      (node (ref "Q117") (pin "1") (pinfunction "G_1") (pintype "bidirectional"))
      (node (ref "R57") (pin "1") (pinfunction "1_1") (pintype "passive"))
    )
    (net (code "2") (name "/N$5") (class "Default")
      (node (ref "Q144") (pin "1") (pinfunction "G_1") (pintype "bidirectional"))
      (node (ref "Q145") (pin "1") (pinfunction "G_1") (pintype "bidirectional"))
      (node (ref "Q156") (pin "3") (pinfunction "D_3") (pintype "bidirectional"))
      (node (ref "Q157") (pin "3") (pinfunction "D_3") (pintype "bidirectional"))
      (node (ref "Q158") (pin "1") (pinfunction "G_1") (pintype "bidirectional"))
      (node (ref "R81") (pin "1") (pinfunction "1_1") (pintype "passive"))
    )
    (net (code "3") (name "/N$9") (class "Default")
      (node (ref "Q1") (pin "3") (pinfunction "D_3") (pintype "bidirectional"))
      (node (ref "Q2") (pin "3") (pinfunction "D_3") (pintype "bidirectional"))
      (node (ref "Q22") (pin "1") (pinfunction "G_1") (pintype "bidirectional"))
      (node (ref "Q5") (pin "1") (pinfunction "G_1") (pintype "bidirectional"))
      (node (ref "Q6") (pin "1") (pinfunction "G_1") (pintype "bidirectional"))
      (node (ref "R1") (pin "1") (pinfunction "1_1") (pintype "passive"))
    )
    (net (code "4") (name "/N$10") (class "Default")
      (node (ref "Q12") (pin "1") (pinfunction "G_1") (pintype "bidirectional"))
      (node (ref "Q13") (pin "1") (pinfunction "G_1") (pintype "bidirectional"))
      (node (ref "Q19") (pin "3") (pinfunction "D_3") (pintype "bidirectional"))
      (node (ref "Q20") (pin "3") (pinfunction "D_3") (pintype "bidirectional"))
      (node (ref "Q21") (pin "1") (pinfunction "G_1") (pintype "bidirectional"))
      (node (ref "R9") (pin "1") (pinfunction "1_1") (pintype "passive"))
    )
    (net (code "5") (name "/N$11") (class "Default")
      (node (ref "Q10") (pin "3") (pinfunction "D_3") (pintype "bidirectional"))
      (node (ref "Q11") (pin "1") (pinfunction "G_1") (pintype "bidirectional"))
      (node (ref "Q19") (pin "1") (pinfunction "G_1") (pintype "bidirectional"))
      (node (ref "Q9") (pin "3") (pinfunction "D_3") (pintype "bidirectional"))
      (node (ref "R5") (pin "1") (pinfunction "1_1") (pintype "passive"))
    )
    (net (code "6") (name "/N$12") (class "Default")
      (node (ref "Q10") (pin "1") (pinfunction "G_1") (pintype "bidirectional"))
      (node (ref "Q6") (pin "3") (pinfunction "D_3") (pintype "bidirectional"))
      (node (ref "Q7") (pin "3") (pinfunction "D_3") (pintype "bidirectional"))
      (node (ref "R3") (pin "1") (pinfunction "1_1") (pintype "passive"))
    )
    (net (code "7") (name "/N$13") (class "Default")
      (node (ref "Q3") (pin "3") (pinfunction "D_3") (pintype "bidirectional"))
      (node (ref "Q5") (pin "3") (pinfunction "D_3") (pintype "bidirectional"))
      (node (ref "Q9") (pin "1") (pinfunction "G_1") (pintype "bidirectional"))
      (node (ref "R2") (pin "1") (pinfunction "1_1") (pintype "passive"))
    )
    (net (code "8") (name "/N$14") (class "Default")
      (node (ref "Q11") (pin "3") (pinfunction "D_3") (pintype "bidirectional"))
      (node (ref "Q12") (pin "3") (pinfunction "D_3") (pintype "bidirectional"))
      (node (ref "Q17") (pin "1") (pinfunction "G_1") (pintype "bidirectional"))
      (node (ref "R6") (pin "1") (pinfunction "1_1") (pintype "passive"))
    )
    (net (code "9") (name "/N$19") (class "Default")
      (node (ref "Q33") (pin "3") (pinfunction "D_3") (pintype "bidirectional"))
      (node (ref "Q34") (pin "3") (pinfunction "D_3") (pintype "bidirectional"))
      (node (ref "Q35") (pin "1") (pinfunction "G_1") (pintype "bidirectional"))
      (node (ref "Q43") (pin "1") (pinfunction "G_1") (pintype "bidirectional"))
      (node (ref "R17") (pin "1") (pinfunction "1_1") (pintype "passive"))
    )
    (net (code "10") (name "/N$20") (class "Default")
      (node (ref "Q30") (pin "3") (pinfunction "D_3") (pintype "bidirectional"))
      (node (ref "Q31") (pin "3") (pinfunction "D_3") (pintype "bidirectional"))
      (node (ref "Q34") (pin "1") (pinfunction "G_1") (pintype "bidirectional"))
      (node (ref "R15") (pin "1") (pinfunction "1_1") (pintype "passive"))
    )
    (net (code "11") (name "/N$21") (class "Default")
      (node (ref "Q27") (pin "3") (pinfunction "D_3") (pintype "bidirectional"))
      (node (ref "Q29") (pin "3") (pinfunction "D_3") (pintype "bidirectional"))
      (node (ref "Q33") (pin "1") (pinfunction "G_1") (pintype "bidirectional"))
      (node (ref "R14") (pin "1") (pinfunction "1_1") (pintype "passive"))
    )
    (net (code "12") (name "/N$22") (class "Default")
      (node (ref "Q47") (pin "3") (pinfunction "D_3") (pintype "bidirectional"))
      (node (ref "Q48") (pin "3") (pinfunction "D_3") (pintype "bidirectional"))
      (node (ref "Q53") (pin "1") (pinfunction "G_1") (pintype "bidirectional"))
      (node (ref "Q54") (pin "1") (pinfunction "G_1") (pintype "bidirectional"))
      (node (ref "Q71") (pin "1") (pinfunction "G_1") (pintype "bidirectional"))
      (node (ref "R24") (pin "1") (pinfunction "1_1") (pintype "passive"))
    )
    (net (code "13") (name "/N$23") (class "Default")
      (node (ref "Q56") (pin "3") (pinfunction "D_3") (pintype "bidirectional"))
      (node (ref "Q57") (pin "3") (pinfunction "D_3") (pintype "bidirectional"))
      (node (ref "Q58") (pin "1") (pinfunction "G_1") (pintype "bidirectional"))
      (node (ref "Q67") (pin "1") (pinfunction "G_1") (pintype "bidirectional"))
      (node (ref "R27") (pin "1") (pinfunction "1_1") (pintype "passive"))
    )
    (net (code "14") (name "/N$24") (class "Default")
      (node (ref "Q54") (pin "3") (pinfunction "D_3") (pintype "bidirectional"))
      (node (ref "Q55") (pin "3") (pinfunction "D_3") (pintype "bidirectional"))
      (node (ref "Q57") (pin "1") (pinfunction "G_1") (pintype "bidirectional"))
      (node (ref "R26") (pin "1") (pinfunction "1_1") (pintype "passive"))
    )
    (net (code "15") (name "/N$25") (class "Default")
      (node (ref "Q49") (pin "3") (pinfunction "D_3") (pintype "bidirectional"))
      (node (ref "Q53") (pin "3") (pinfunction "D_3") (pintype "bidirectional"))
      (node (ref "Q56") (pin "1") (pinfunction "G_1") (pintype "bidirectional"))
      (node (ref "R25") (pin "1") (pinfunction "1_1") (pintype "passive"))
    )
    (net (code "16") (name "/N$26") (class "Default")
      (node (ref "Q59") (pin "1") (pinfunction "G_1") (pintype "bidirectional"))
      (node (ref "Q60") (pin "1") (pinfunction "G_1") (pintype "bidirectional"))
      (node (ref "Q67") (pin "3") (pinfunction "D_3") (pintype "bidirectional"))
      (node (ref "Q69") (pin "3") (pinfunction "D_3") (pintype "bidirectional"))
      (node (ref "Q70") (pin "1") (pinfunction "G_1") (pintype "bidirectional"))
      (node (ref "R34") (pin "1") (pinfunction "1_1") (pintype "passive"))
    )
    (net (code "17") (name "/N$28") (class "Default")
      (node (ref "Q58") (pin "3") (pinfunction "D_3") (pintype "bidirectional"))
      (node (ref "Q59") (pin "3") (pinfunction "D_3") (pintype "bidirectional"))
      (node (ref "Q65") (pin "1") (pinfunction "G_1") (pintype "bidirectional"))
      (node (ref "R28") (pin "1") (pinfunction "1_1") (pintype "passive"))
    )
    (net (code "18") (name "/N$44") (class "Default")
      (node (ref "Q106") (pin "1") (pinfunction "G_1") (pintype "bidirectional"))
      (node (ref "Q97") (pin "3") (pinfunction "D_3") (pintype "bidirectional"))
      (node (ref "Q98") (pin "3") (pinfunction "D_3") (pintype "bidirectional"))
      (node (ref "Q99") (pin "1") (pinfunction "G_1") (pintype "bidirectional"))
      (node (ref "R49") (pin "1") (pinfunction "1_1") (pintype "passive"))
    )
    (net (code "19") (name "/N$55") (class "Default")
      (node (ref "Q100") (pin "1") (pinfunction "G_1") (pintype "bidirectional"))
      (node (ref "Q101") (pin "1") (pinfunction "G_1") (pintype "bidirectional"))
      (node (ref "Q106") (pin "3") (pinfunction "D_3") (pintype "bidirectional"))
      (node (ref "Q107") (pin "3") (pinfunction "D_3") (pintype "bidirectional"))
      (node (ref "Q108") (pin "1") (pinfunction "G_1") (pintype "bidirectional"))
      (node (ref "R53") (pin "1") (pinfunction "1_1") (pintype "passive"))
    )
    (net (code "20") (name "/N$101") (class "Default")
      (node (ref "Q128") (pin "3") (pinfunction "D_3") (pintype "bidirectional"))
      (node (ref "Q129") (pin "3") (pinfunction "D_3") (pintype "bidirectional"))
      (node (ref "Q131") (pin "1") (pinfunction "G_1") (pintype "bidirectional"))
      (node (ref "Q132") (pin "1") (pinfunction "G_1") (pintype "bidirectional"))
      (node (ref "Q159") (pin "1") (pinfunction "G_1") (pintype "bidirectional"))
      (node (ref "R66") (pin "1") (pinfunction "1_1") (pintype "passive"))
    )
    (net (code "21") (name "/N$102") (class "Default")
      (node (ref "Q132") (pin "3") (pinfunction "D_3") (pintype "bidirectional"))
      (node (ref "Q133") (pin "3") (pinfunction "D_3") (pintype "bidirectional"))
      (node (ref "Q142") (pin "1") (pinfunction "G_1") (pintype "bidirectional"))
      (node (ref "R72") (pin "1") (pinfunction "1_1") (pintype "passive"))
    )
    (net (code "22") (name "/N$104") (class "Default")
      (node (ref "Q141") (pin "3") (pinfunction "D_3") (pintype "bidirectional"))
      (node (ref "Q142") (pin "3") (pinfunction "D_3") (pintype "bidirectional"))
      (node (ref "Q143") (pin "1") (pinfunction "G_1") (pintype "bidirectional"))
      (node (ref "Q156") (pin "1") (pinfunction "G_1") (pintype "bidirectional"))
      (node (ref "R73") (pin "1") (pinfunction "1_1") (pintype "passive"))
    )
    (net (code "23") (name "/N$108") (class "Default")
      (node (ref "Q143") (pin "3") (pinfunction "D_3") (pintype "bidirectional"))
      (node (ref "Q144") (pin "3") (pinfunction "D_3") (pintype "bidirectional"))
      (node (ref "Q147") (pin "1") (pinfunction "G_1") (pintype "bidirectional"))
      (node (ref "R74") (pin "1") (pinfunction "1_1") (pintype "passive"))
    )
    (net (code "24") (name "/N$124") (class "Default")
      (node (ref "Q73") (pin "3") (pinfunction "D_3") (pintype "bidirectional"))
      (node (ref "Q74") (pin "3") (pinfunction "D_3") (pintype "bidirectional"))
      (node (ref "Q76") (pin "1") (pinfunction "G_1") (pintype "bidirectional"))
      (node (ref "Q77") (pin "1") (pinfunction "G_1") (pintype "bidirectional"))
      (node (ref "Q90") (pin "1") (pinfunction "G_1") (pintype "bidirectional"))
      (node (ref "R37") (pin "1") (pinfunction "1_1") (pintype "passive"))
    )
    (net (code "25") (name "/N$152") (class "Default")
      (node (ref "Q110") (pin "3") (pinfunction "D_3") (pintype "bidirectional"))
      (node (ref "Q111") (pin "3") (pinfunction "D_3") (pintype "bidirectional"))
      (node (ref "Q113") (pin "1") (pinfunction "G_1") (pintype "bidirectional"))
      (node (ref "Q115") (pin "1") (pinfunction "G_1") (pintype "bidirectional"))
      (node (ref "R56") (pin "1") (pinfunction "1_1") (pintype "passive"))
    )
    (net (code "26") (name "/N$224") (class "Default")
      (node (ref "Q77") (pin "3") (pinfunction "D_3") (pintype "bidirectional"))
      (node (ref "Q78") (pin "3") (pinfunction "D_3") (pintype "bidirectional"))
      (node (ref "Q80") (pin "1") (pinfunction "G_1") (pintype "bidirectional"))
      (node (ref "R39") (pin "1") (pinfunction "1_1") (pintype "passive"))
    )
    (net (code "27") (name "/N$293") (class "Default")
      (node (ref "Q95") (pin "3") (pinfunction "D_3") (pintype "bidirectional"))
      (node (ref "Q96") (pin "3") (pinfunction "D_3") (pintype "bidirectional"))
      (node (ref "Q98") (pin "1") (pinfunction "G_1") (pintype "bidirectional"))
      (node (ref "R48") (pin "1") (pinfunction "1_1") (pintype "passive"))
    )
    (net (code "28") (name "/N$298") (class "Default")
      (node (ref "Q115") (pin "3") (pinfunction "D_3") (pintype "bidirectional"))
      (node (ref "Q116") (pin "3") (pinfunction "D_3") (pintype "bidirectional"))
      (node (ref "Q118") (pin "1") (pinfunction "G_1") (pintype "bidirectional"))
      (node (ref "R58") (pin "1") (pinfunction "1_1") (pintype "passive"))
    )
    (net (code "29") (name "/N$324") (class "Default")
      (node (ref "Q75") (pin "3") (pinfunction "D_3") (pintype "bidirectional"))
      (node (ref "Q76") (pin "3") (pinfunction "D_3") (pintype "bidirectional"))
      (node (ref "Q79") (pin "1") (pinfunction "G_1") (pintype "bidirectional"))
      (node (ref "R38") (pin "1") (pinfunction "1_1") (pintype "passive"))
    )
    (net (code "30") (name "/N$344") (class "Default")
      (node (ref "Q93") (pin "3") (pinfunction "D_3") (pintype "bidirectional"))
      (node (ref "Q94") (pin "3") (pinfunction "D_3") (pintype "bidirectional"))
      (node (ref "Q97") (pin "1") (pinfunction "G_1") (pintype "bidirectional"))
      (node (ref "R47") (pin "1") (pinfunction "1_1") (pintype "passive"))
    )
    (net (code "31") (name "/N$362") (class "Default")
      (node (ref "Q83") (pin "3") (pinfunction "D_3") (pintype "bidirectional"))
      (node (ref "Q84") (pin "3") (pinfunction "D_3") (pintype "bidirectional"))
      (node (ref "Q86") (pin "1") (pinfunction "G_1") (pintype "bidirectional"))
      (node (ref "R42") (pin "1") (pinfunction "1_1") (pintype "passive"))
    )
    (net (code "32") (name "/N$367") (class "Default")
      (node (ref "Q130") (pin "3") (pinfunction "D_3") (pintype "bidirectional"))
      (node (ref "Q131") (pin "3") (pinfunction "D_3") (pintype "bidirectional"))
      (node (ref "Q141") (pin "1") (pinfunction "G_1") (pintype "bidirectional"))
      (node (ref "R67") (pin "1") (pinfunction "1_1") (pintype "passive"))
    )
    (net (code "33") (name "/N$425") (class "Default")
      (node (ref "Q79") (pin "3") (pinfunction "D_3") (pintype "bidirectional"))
      (node (ref "Q80") (pin "3") (pinfunction "D_3") (pintype "bidirectional"))
      (node (ref "Q81") (pin "1") (pinfunction "G_1") (pintype "bidirectional"))
      (node (ref "Q87") (pin "1") (pinfunction "G_1") (pintype "bidirectional"))
      (node (ref "R40") (pin "1") (pinfunction "1_1") (pintype "passive"))
    )
    (net (code "34") (name "/N$457") (class "Default")
      (node (ref "Q120") (pin "1") (pinfunction "G_1") (pintype "bidirectional"))
      (node (ref "Q121") (pin "1") (pinfunction "G_1") (pintype "bidirectional"))
      (node (ref "Q125") (pin "3") (pinfunction "D_3") (pintype "bidirectional"))
      (node (ref "Q126") (pin "3") (pinfunction "D_3") (pintype "bidirectional"))
      (node (ref "R63") (pin "1") (pinfunction "1_1") (pintype "passive"))
    )
    (net (code "35") (name "/N$477") (class "Default")
      (node (ref "Q117") (pin "3") (pinfunction "D_3") (pintype "bidirectional"))
      (node (ref "Q118") (pin "3") (pinfunction "D_3") (pintype "bidirectional"))
      (node (ref "Q119") (pin "1") (pinfunction "G_1") (pintype "bidirectional"))
      (node (ref "Q125") (pin "1") (pinfunction "G_1") (pintype "bidirectional"))
      (node (ref "R59") (pin "1") (pinfunction "1_1") (pintype "passive"))
    )
    (net (code "36") (name "/N$615") (class "Default")
      (node (ref "Q101") (pin "3") (pinfunction "D_3") (pintype "bidirectional"))
      (node (ref "Q102") (pin "3") (pinfunction "D_3") (pintype "bidirectional"))
      (node (ref "Q104") (pin "1") (pinfunction "G_1") (pintype "bidirectional"))
      (node (ref "R51") (pin "1") (pinfunction "1_1") (pintype "passive"))
    )
    (net (code "37") (name "/N$627") (class "Default")
      (node (ref "Q121") (pin "3") (pinfunction "D_3") (pintype "bidirectional"))
      (node (ref "Q122") (pin "3") (pinfunction "D_3") (pintype "bidirectional"))
      (node (ref "Q124") (pin "1") (pinfunction "G_1") (pintype "bidirectional"))
      (node (ref "R61") (pin "1") (pinfunction "1_1") (pintype "passive"))
    )
    (net (code "38") (name "/N$713") (class "Default")
      (node (ref "Q119") (pin "3") (pinfunction "D_3") (pintype "bidirectional"))
      (node (ref "Q120") (pin "3") (pinfunction "D_3") (pintype "bidirectional"))
      (node (ref "Q123") (pin "1") (pinfunction "G_1") (pintype "bidirectional"))
      (node (ref "R60") (pin "1") (pinfunction "1_1") (pintype "passive"))
    )
    (net (code "39") (name "/N$715") (class "Default")
      (node (ref "Q100") (pin "3") (pinfunction "D_3") (pintype "bidirectional"))
      (node (ref "Q103") (pin "1") (pinfunction "G_1") (pintype "bidirectional"))
      (node (ref "Q99") (pin "3") (pinfunction "D_3") (pintype "bidirectional"))
      (node (ref "R50") (pin "1") (pinfunction "1_1") (pintype "passive"))
    )
    (net (code "40") (name "/N$768") (class "Default")
      (node (ref "Q81") (pin "3") (pinfunction "D_3") (pintype "bidirectional"))
      (node (ref "Q82") (pin "3") (pinfunction "D_3") (pintype "bidirectional"))
      (node (ref "Q85") (pin "1") (pinfunction "G_1") (pintype "bidirectional"))
      (node (ref "R41") (pin "1") (pinfunction "1_1") (pintype "passive"))
    )
    (net (code "41") (name "/N$1016") (class "Default")
      (node (ref "Q37") (pin "1") (pinfunction "G_1") (pintype "bidirectional"))
      (node (ref "Q38") (pin "1") (pinfunction "G_1") (pintype "bidirectional"))
      (node (ref "Q43") (pin "3") (pinfunction "D_3") (pintype "bidirectional"))
      (node (ref "Q44") (pin "3") (pinfunction "D_3") (pintype "bidirectional"))
      (node (ref "Q45") (pin "1") (pinfunction "G_1") (pintype "bidirectional"))
      (node (ref "R22") (pin "1") (pinfunction "1_1") (pintype "passive"))
    )
    (net (code "42") (name "/N$1017") (class "Default")
      (node (ref "Q25") (pin "3") (pinfunction "D_3") (pintype "bidirectional"))
      (node (ref "Q26") (pin "3") (pinfunction "D_3") (pintype "bidirectional"))
      (node (ref "Q29") (pin "1") (pinfunction "G_1") (pintype "bidirectional"))
      (node (ref "Q30") (pin "1") (pinfunction "G_1") (pintype "bidirectional"))
      (node (ref "Q46") (pin "1") (pinfunction "G_1") (pintype "bidirectional"))
      (node (ref "R13") (pin "1") (pinfunction "1_1") (pintype "passive"))
    )
    (net (code "43") (name "/N$1257") (class "Default")
      (node (ref "Q109") (pin "1") (pinfunction "G_1") (pintype "bidirectional"))
      (node (ref "Q91") (pin "3") (pinfunction "D_3") (pintype "bidirectional"))
      (node (ref "Q92") (pin "3") (pinfunction "D_3") (pintype "bidirectional"))
      (node (ref "Q94") (pin "1") (pinfunction "G_1") (pintype "bidirectional"))
      (node (ref "Q95") (pin "1") (pinfunction "G_1") (pintype "bidirectional"))
      (node (ref "R46") (pin "1") (pinfunction "1_1") (pintype "passive"))
    )
    (net (code "44") (name "/N$5234") (class "Default")
      (node (ref "Q82") (pin "1") (pinfunction "G_1") (pintype "bidirectional"))
      (node (ref "Q83") (pin "1") (pinfunction "G_1") (pintype "bidirectional"))
      (node (ref "Q87") (pin "3") (pinfunction "D_3") (pintype "bidirectional"))
      (node (ref "Q88") (pin "3") (pinfunction "D_3") (pintype "bidirectional"))
      (node (ref "Q89") (pin "1") (pinfunction "G_1") (pintype "bidirectional"))
      (node (ref "R44") (pin "1") (pinfunction "1_1") (pintype "passive"))
    )
    (net (code "45") (name "/N12") (class "Default")
      (node (ref "Q35") (pin "3") (pinfunction "D_3") (pintype "bidirectional"))
      (node (ref "Q37") (pin "3") (pinfunction "D_3") (pintype "bidirectional"))
      (node (ref "Q41") (pin "1") (pinfunction "G_1") (pintype "bidirectional"))
      (node (ref "R18") (pin "1") (pinfunction "1_1") (pintype "passive"))
    )
    (net (code "46") (name "A0") (class "Default")
      (node (ref "J1") (pin "1") (pinfunction "1_1") (pintype "passive"))
      (node (ref "Q128") (pin "1") (pinfunction "G_1") (pintype "bidirectional"))
      (node (ref "Q130") (pin "1") (pinfunction "G_1") (pintype "bidirectional"))
    )
    (net (code "47") (name "A1") (class "Default")
      (node (ref "J1") (pin "2") (pinfunction "2_2") (pintype "passive"))
      (node (ref "Q1") (pin "1") (pinfunction "G_1") (pintype "bidirectional"))
      (node (ref "Q3") (pin "1") (pinfunction "G_1") (pintype "bidirectional"))
    )
    (net (code "48") (name "A2") (class "Default")
      (node (ref "J1") (pin "3") (pinfunction "3_3") (pintype "passive"))
      (node (ref "Q25") (pin "1") (pinfunction "G_1") (pintype "bidirectional"))
      (node (ref "Q27") (pin "1") (pinfunction "G_1") (pintype "bidirectional"))
    )
    (net (code "49") (name "A3") (class "Default")
      (node (ref "J1") (pin "4") (pinfunction "4_4") (pintype "passive"))
      (node (ref "Q47") (pin "1") (pinfunction "G_1") (pintype "bidirectional"))
      (node (ref "Q49") (pin "1") (pinfunction "G_1") (pintype "bidirectional"))
    )
    (net (code "50") (name "B0") (class "Default")
      (node (ref "J1") (pin "5") (pinfunction "5_5") (pintype "passive"))
      (node (ref "Q148") (pin "1") (pinfunction "G_1") (pintype "bidirectional"))
      (node (ref "Q63") (pin "1") (pinfunction "G_1") (pintype "bidirectional"))
    )
    (net (code "51") (name "B0'") (class "Default")
      (node (ref "Q129") (pin "1") (pinfunction "G_1") (pintype "bidirectional"))
      (node (ref "Q133") (pin "1") (pinfunction "G_1") (pintype "bidirectional"))
      (node (ref "Q149") (pin "3") (pinfunction "D_3") (pintype "bidirectional"))
      (node (ref "Q150") (pin "3") (pinfunction "D_3") (pintype "bidirectional"))
      (node (ref "R78") (pin "1") (pinfunction "1_1") (pintype "passive"))
    )
    (net (code "52") (name "B1") (class "Default")
      (node (ref "J1") (pin "6") (pinfunction "6_6") (pintype "passive"))
      (node (ref "Q23") (pin "1") (pinfunction "G_1") (pintype "bidirectional"))
      (node (ref "Q4") (pin "1") (pinfunction "G_1") (pintype "bidirectional"))
    )
    (net (code "53") (name "B1'") (class "Default")
      (node (ref "Q2") (pin "1") (pinfunction "G_1") (pintype "bidirectional"))
      (node (ref "Q24") (pin "3") (pinfunction "D_3") (pintype "bidirectional"))
      (node (ref "Q28") (pin "3") (pinfunction "D_3") (pintype "bidirectional"))
      (node (ref "Q7") (pin "1") (pinfunction "G_1") (pintype "bidirectional"))
      (node (ref "R16") (pin "1") (pinfunction "1_1") (pintype "passive"))
    )
    (net (code "54") (name "B2") (class "Default")
      (node (ref "J1") (pin "7") (pinfunction "7_7") (pintype "passive"))
      (node (ref "Q163") (pin "1") (pinfunction "G_1") (pintype "bidirectional"))
      (node (ref "Q167") (pin "1") (pinfunction "G_1") (pintype "bidirectional"))
    )
    (net (code "55") (name "B2'") (class "Default")
      (node (ref "Q168") (pin "3") (pinfunction "D_3") (pintype "bidirectional"))
      (node (ref "Q169") (pin "3") (pinfunction "D_3") (pintype "bidirectional"))
      (node (ref "Q26") (pin "1") (pinfunction "G_1") (pintype "bidirectional"))
      (node (ref "Q31") (pin "1") (pinfunction "G_1") (pintype "bidirectional"))
      (node (ref "R89") (pin "1") (pinfunction "1_1") (pintype "passive"))
    )
    (net (code "56") (name "B3") (class "Default")
      (node (ref "J1") (pin "8") (pinfunction "8_8") (pintype "passive"))
      (node (ref "Q177") (pin "1") (pinfunction "G_1") (pintype "bidirectional"))
      (node (ref "Q181") (pin "1") (pinfunction "G_1") (pintype "bidirectional"))
    )
    (net (code "57") (name "B3'") (class "Default")
      (node (ref "Q182") (pin "3") (pinfunction "D_3") (pintype "bidirectional"))
      (node (ref "Q183") (pin "3") (pinfunction "D_3") (pintype "bidirectional"))
      (node (ref "Q48") (pin "1") (pinfunction "G_1") (pintype "bidirectional"))
      (node (ref "Q55") (pin "1") (pinfunction "G_1") (pintype "bidirectional"))
      (node (ref "R97") (pin "1") (pinfunction "1_1") (pintype "passive"))
    )
    (net (code "58") (name "C01") (class "Default")
      (node (ref "Q14") (pin "1") (pinfunction "G_1") (pintype "bidirectional"))
      (node (ref "Q158") (pin "3") (pinfunction "D_3") (pintype "bidirectional"))
      (node (ref "Q159") (pin "3") (pinfunction "D_3") (pintype "bidirectional"))
      (node (ref "Q20") (pin "1") (pinfunction "G_1") (pintype "bidirectional"))
      (node (ref "R82") (pin "1") (pinfunction "1_1") (pintype "passive"))
    )
    (net (code "59") (name "C12") (class "Default")
      (node (ref "Q21") (pin "3") (pinfunction "D_3") (pintype "bidirectional"))
      (node (ref "Q22") (pin "3") (pinfunction "D_3") (pintype "bidirectional"))
      (node (ref "Q39") (pin "1") (pinfunction "G_1") (pintype "bidirectional"))
      (node (ref "Q44") (pin "1") (pinfunction "G_1") (pintype "bidirectional"))
      (node (ref "R10") (pin "1") (pinfunction "1_1") (pintype "passive"))
    )
    (net (code "60") (name "C23") (class "Default")
      (node (ref "Q45") (pin "3") (pinfunction "D_3") (pintype "bidirectional"))
      (node (ref "Q46") (pin "3") (pinfunction "D_3") (pintype "bidirectional"))
      (node (ref "Q61") (pin "1") (pinfunction "G_1") (pintype "bidirectional"))
      (node (ref "Q69") (pin "1") (pinfunction "G_1") (pintype "bidirectional"))
      (node (ref "R23") (pin "1") (pinfunction "1_1") (pintype "passive"))
    )
    (net (code "61") (name "C45") (class "Default")
      (node (ref "Q102") (pin "1") (pinfunction "G_1") (pintype "bidirectional"))
      (node (ref "Q107") (pin "1") (pinfunction "G_1") (pintype "bidirectional"))
      (node (ref "Q89") (pin "3") (pinfunction "D_3") (pintype "bidirectional"))
      (node (ref "Q90") (pin "3") (pinfunction "D_3") (pintype "bidirectional"))
      (node (ref "R45") (pin "1") (pinfunction "1_1") (pintype "passive"))
    )
    (net (code "62") (name "C56") (class "Default")
      (node (ref "Q108") (pin "3") (pinfunction "D_3") (pintype "bidirectional"))
      (node (ref "Q109") (pin "3") (pinfunction "D_3") (pintype "bidirectional"))
      (node (ref "Q122") (pin "1") (pinfunction "G_1") (pintype "bidirectional"))
      (node (ref "Q126") (pin "1") (pinfunction "G_1") (pintype "bidirectional"))
      (node (ref "R55") (pin "1") (pinfunction "1_1") (pintype "passive"))
    )
    (net (code "63") (name "CRYIN") (class "Default")
      (node (ref "J1") (pin "9") (pinfunction "9_9") (pintype "passive"))
      (node (ref "Q146") (pin "1") (pinfunction "G_1") (pintype "bidirectional"))
      (node (ref "Q157") (pin "1") (pinfunction "G_1") (pintype "bidirectional"))
    )
    (net (code "64") (name "CRYOUT") (class "Default")
      (node (ref "J1") (pin "14") (pinfunction "14_14") (pintype "passive"))
      (node (ref "Q114") (pin "1") (pinfunction "G_1") (pintype "bidirectional"))
      (node (ref "Q70") (pin "3") (pinfunction "D_3") (pintype "bidirectional"))
      (node (ref "Q71") (pin "3") (pinfunction "D_3") (pintype "bidirectional"))
      (node (ref "Q74") (pin "1") (pinfunction "G_1") (pintype "bidirectional"))
      (node (ref "Q78") (pin "1") (pinfunction "G_1") (pintype "bidirectional"))
      (node (ref "R35") (pin "1") (pinfunction "1_1") (pintype "passive"))
    )
    (net (code "65") (name "GND") (class "Default")
      (node (ref "C14") (pin "2") (pinfunction "2_2") (pintype "passive"))
      (node (ref "J1") (pin "20") (pinfunction "20_20") (pintype "passive"))
      (node (ref "Q1") (pin "2") (pinfunction "S_2") (pintype "bidirectional"))
      (node (ref "Q10") (pin "2") (pinfunction "S_2") (pintype "bidirectional"))
      (node (ref "Q100") (pin "2") (pinfunction "S_2") (pintype "bidirectional"))
      (node (ref "Q101") (pin "2") (pinfunction "S_2") (pintype "bidirectional"))
      (node (ref "Q102") (pin "2") (pinfunction "S_2") (pintype "bidirectional"))
      (node (ref "Q103") (pin "2") (pinfunction "S_2") (pintype "bidirectional"))
      (node (ref "Q104") (pin "2") (pinfunction "S_2") (pintype "bidirectional"))
      (node (ref "Q105") (pin "2") (pinfunction "S_2") (pintype "bidirectional"))
      (node (ref "Q106") (pin "2") (pinfunction "S_2") (pintype "bidirectional"))
      (node (ref "Q107") (pin "2") (pinfunction "S_2") (pintype "bidirectional"))
      (node (ref "Q108") (pin "2") (pinfunction "S_2") (pintype "bidirectional"))
      (node (ref "Q109") (pin "2") (pinfunction "S_2") (pintype "bidirectional"))
      (node (ref "Q11") (pin "2") (pinfunction "S_2") (pintype "bidirectional"))
      (node (ref "Q110") (pin "2") (pinfunction "S_2") (pintype "bidirectional"))
      (node (ref "Q111") (pin "2") (pinfunction "S_2") (pintype "bidirectional"))
      (node (ref "Q112") (pin "2") (pinfunction "S_2") (pintype "bidirectional"))
      (node (ref "Q113") (pin "2") (pinfunction "S_2") (pintype "bidirectional"))
      (node (ref "Q114") (pin "2") (pinfunction "S_2") (pintype "bidirectional"))
      (node (ref "Q115") (pin "2") (pinfunction "S_2") (pintype "bidirectional"))
      (node (ref "Q116") (pin "2") (pinfunction "S_2") (pintype "bidirectional"))
      (node (ref "Q117") (pin "2") (pinfunction "S_2") (pintype "bidirectional"))
      (node (ref "Q118") (pin "2") (pinfunction "S_2") (pintype "bidirectional"))
      (node (ref "Q119") (pin "2") (pinfunction "S_2") (pintype "bidirectional"))
      (node (ref "Q12") (pin "2") (pinfunction "S_2") (pintype "bidirectional"))
      (node (ref "Q120") (pin "2") (pinfunction "S_2") (pintype "bidirectional"))
      (node (ref "Q121") (pin "2") (pinfunction "S_2") (pintype "bidirectional"))
      (node (ref "Q122") (pin "2") (pinfunction "S_2") (pintype "bidirectional"))
      (node (ref "Q123") (pin "2") (pinfunction "S_2") (pintype "bidirectional"))
      (node (ref "Q124") (pin "2") (pinfunction "S_2") (pintype "bidirectional"))
      (node (ref "Q125") (pin "2") (pinfunction "S_2") (pintype "bidirectional"))
      (node (ref "Q126") (pin "2") (pinfunction "S_2") (pintype "bidirectional"))
      (node (ref "Q127") (pin "2") (pinfunction "S_2") (pintype "bidirectional"))
      (node (ref "Q128") (pin "2") (pinfunction "S_2") (pintype "bidirectional"))
      (node (ref "Q129") (pin "2") (pinfunction "S_2") (pintype "bidirectional"))
      (node (ref "Q13") (pin "2") (pinfunction "S_2") (pintype "bidirectional"))
      (node (ref "Q130") (pin "2") (pinfunction "S_2") (pintype "bidirectional"))
      (node (ref "Q131") (pin "2") (pinfunction "S_2") (pintype "bidirectional"))
      (node (ref "Q132") (pin "2") (pinfunction "S_2") (pintype "bidirectional"))
      (node (ref "Q133") (pin "2") (pinfunction "S_2") (pintype "bidirectional"))
      (node (ref "Q14") (pin "2") (pinfunction "S_2") (pintype "bidirectional"))
      (node (ref "Q141") (pin "2") (pinfunction "S_2") (pintype "bidirectional"))
      (node (ref "Q142") (pin "2") (pinfunction "S_2") (pintype "bidirectional"))
      (node (ref "Q143") (pin "2") (pinfunction "S_2") (pintype "bidirectional"))
      (node (ref "Q144") (pin "2") (pinfunction "S_2") (pintype "bidirectional"))
      (node (ref "Q145") (pin "2") (pinfunction "S_2") (pintype "bidirectional"))
      (node (ref "Q146") (pin "2") (pinfunction "S_2") (pintype "bidirectional"))
      (node (ref "Q147") (pin "2") (pinfunction "S_2") (pintype "bidirectional"))
      (node (ref "Q148") (pin "2") (pinfunction "S_2") (pintype "bidirectional"))
      (node (ref "Q149") (pin "2") (pinfunction "S_2") (pintype "bidirectional"))
      (node (ref "Q15") (pin "2") (pinfunction "S_2") (pintype "bidirectional"))
      (node (ref "Q150") (pin "2") (pinfunction "S_2") (pintype "bidirectional"))
      (node (ref "Q155") (pin "2") (pinfunction "S_2") (pintype "bidirectional"))
      (node (ref "Q156") (pin "2") (pinfunction "S_2") (pintype "bidirectional"))
      (node (ref "Q157") (pin "2") (pinfunction "S_2") (pintype "bidirectional"))
      (node (ref "Q158") (pin "2") (pinfunction "S_2") (pintype "bidirectional"))
      (node (ref "Q159") (pin "2") (pinfunction "S_2") (pintype "bidirectional"))
      (node (ref "Q16") (pin "2") (pinfunction "S_2") (pintype "bidirectional"))
      (node (ref "Q163") (pin "2") (pinfunction "S_2") (pintype "bidirectional"))
      (node (ref "Q164") (pin "2") (pinfunction "S_2") (pintype "bidirectional"))
      (node (ref "Q165") (pin "2") (pinfunction "S_2") (pintype "bidirectional"))
      (node (ref "Q166") (pin "2") (pinfunction "S_2") (pintype "bidirectional"))
      (node (ref "Q167") (pin "2") (pinfunction "S_2") (pintype "bidirectional"))
      (node (ref "Q168") (pin "2") (pinfunction "S_2") (pintype "bidirectional"))
      (node (ref "Q169") (pin "2") (pinfunction "S_2") (pintype "bidirectional"))
      (node (ref "Q17") (pin "2") (pinfunction "S_2") (pintype "bidirectional"))
      (node (ref "Q177") (pin "2") (pinfunction "S_2") (pintype "bidirectional"))
      (node (ref "Q178") (pin "2") (pinfunction "S_2") (pintype "bidirectional"))
      (node (ref "Q179") (pin "2") (pinfunction "S_2") (pintype "bidirectional"))
      (node (ref "Q18") (pin "2") (pinfunction "S_2") (pintype "bidirectional"))
      (node (ref "Q180") (pin "2") (pinfunction "S_2") (pintype "bidirectional"))
      (node (ref "Q181") (pin "2") (pinfunction "S_2") (pintype "bidirectional"))
      (node (ref "Q182") (pin "2") (pinfunction "S_2") (pintype "bidirectional"))
      (node (ref "Q183") (pin "2") (pinfunction "S_2") (pintype "bidirectional"))
      (node (ref "Q19") (pin "2") (pinfunction "S_2") (pintype "bidirectional"))
      (node (ref "Q2") (pin "2") (pinfunction "S_2") (pintype "bidirectional"))
      (node (ref "Q20") (pin "2") (pinfunction "S_2") (pintype "bidirectional"))
      (node (ref "Q21") (pin "2") (pinfunction "S_2") (pintype "bidirectional"))
      (node (ref "Q22") (pin "2") (pinfunction "S_2") (pintype "bidirectional"))
      (node (ref "Q23") (pin "2") (pinfunction "S_2") (pintype "bidirectional"))
      (node (ref "Q24") (pin "2") (pinfunction "S_2") (pintype "bidirectional"))
      (node (ref "Q25") (pin "2") (pinfunction "S_2") (pintype "bidirectional"))
      (node (ref "Q26") (pin "2") (pinfunction "S_2") (pintype "bidirectional"))
      (node (ref "Q27") (pin "2") (pinfunction "S_2") (pintype "bidirectional"))
      (node (ref "Q28") (pin "2") (pinfunction "S_2") (pintype "bidirectional"))
      (node (ref "Q29") (pin "2") (pinfunction "S_2") (pintype "bidirectional"))
      (node (ref "Q3") (pin "2") (pinfunction "S_2") (pintype "bidirectional"))
      (node (ref "Q30") (pin "2") (pinfunction "S_2") (pintype "bidirectional"))
      (node (ref "Q31") (pin "2") (pinfunction "S_2") (pintype "bidirectional"))
      (node (ref "Q33") (pin "2") (pinfunction "S_2") (pintype "bidirectional"))
      (node (ref "Q34") (pin "2") (pinfunction "S_2") (pintype "bidirectional"))
      (node (ref "Q35") (pin "2") (pinfunction "S_2") (pintype "bidirectional"))
      (node (ref "Q37") (pin "2") (pinfunction "S_2") (pintype "bidirectional"))
      (node (ref "Q38") (pin "2") (pinfunction "S_2") (pintype "bidirectional"))
      (node (ref "Q39") (pin "2") (pinfunction "S_2") (pintype "bidirectional"))
      (node (ref "Q4") (pin "2") (pinfunction "S_2") (pintype "bidirectional"))
      (node (ref "Q41") (pin "2") (pinfunction "S_2") (pintype "bidirectional"))
      (node (ref "Q42") (pin "2") (pinfunction "S_2") (pintype "bidirectional"))
      (node (ref "Q43") (pin "2") (pinfunction "S_2") (pintype "bidirectional"))
      (node (ref "Q44") (pin "2") (pinfunction "S_2") (pintype "bidirectional"))
      (node (ref "Q45") (pin "2") (pinfunction "S_2") (pintype "bidirectional"))
      (node (ref "Q46") (pin "2") (pinfunction "S_2") (pintype "bidirectional"))
      (node (ref "Q47") (pin "2") (pinfunction "S_2") (pintype "bidirectional"))
      (node (ref "Q48") (pin "2") (pinfunction "S_2") (pintype "bidirectional"))
      (node (ref "Q49") (pin "2") (pinfunction "S_2") (pintype "bidirectional"))
      (node (ref "Q5") (pin "2") (pinfunction "S_2") (pintype "bidirectional"))
      (node (ref "Q53") (pin "2") (pinfunction "S_2") (pintype "bidirectional"))
      (node (ref "Q54") (pin "2") (pinfunction "S_2") (pintype "bidirectional"))
      (node (ref "Q55") (pin "2") (pinfunction "S_2") (pintype "bidirectional"))
      (node (ref "Q56") (pin "2") (pinfunction "S_2") (pintype "bidirectional"))
      (node (ref "Q57") (pin "2") (pinfunction "S_2") (pintype "bidirectional"))
      (node (ref "Q58") (pin "2") (pinfunction "S_2") (pintype "bidirectional"))
      (node (ref "Q59") (pin "2") (pinfunction "S_2") (pintype "bidirectional"))
      (node (ref "Q6") (pin "2") (pinfunction "S_2") (pintype "bidirectional"))
      (node (ref "Q60") (pin "2") (pinfunction "S_2") (pintype "bidirectional"))
      (node (ref "Q61") (pin "2") (pinfunction "S_2") (pintype "bidirectional"))
      (node (ref "Q63") (pin "2") (pinfunction "S_2") (pintype "bidirectional"))
      (node (ref "Q64") (pin "2") (pinfunction "S_2") (pintype "bidirectional"))
      (node (ref "Q65") (pin "2") (pinfunction "S_2") (pintype "bidirectional"))
      (node (ref "Q66") (pin "2") (pinfunction "S_2") (pintype "bidirectional"))
      (node (ref "Q67") (pin "2") (pinfunction "S_2") (pintype "bidirectional"))
      (node (ref "Q68") (pin "2") (pinfunction "S_2") (pintype "bidirectional"))
      (node (ref "Q69") (pin "2") (pinfunction "S_2") (pintype "bidirectional"))
      (node (ref "Q7") (pin "2") (pinfunction "S_2") (pintype "bidirectional"))
      (node (ref "Q70") (pin "2") (pinfunction "S_2") (pintype "bidirectional"))
      (node (ref "Q71") (pin "2") (pinfunction "S_2") (pintype "bidirectional"))
      (node (ref "Q72") (pin "2") (pinfunction "S_2") (pintype "bidirectional"))
      (node (ref "Q73") (pin "2") (pinfunction "S_2") (pintype "bidirectional"))
      (node (ref "Q74") (pin "2") (pinfunction "S_2") (pintype "bidirectional"))
      (node (ref "Q75") (pin "2") (pinfunction "S_2") (pintype "bidirectional"))
      (node (ref "Q76") (pin "2") (pinfunction "S_2") (pintype "bidirectional"))
      (node (ref "Q77") (pin "2") (pinfunction "S_2") (pintype "bidirectional"))
      (node (ref "Q78") (pin "2") (pinfunction "S_2") (pintype "bidirectional"))
      (node (ref "Q79") (pin "2") (pinfunction "S_2") (pintype "bidirectional"))
      (node (ref "Q8") (pin "2") (pinfunction "S_2") (pintype "bidirectional"))
      (node (ref "Q80") (pin "2") (pinfunction "S_2") (pintype "bidirectional"))
      (node (ref "Q81") (pin "2") (pinfunction "S_2") (pintype "bidirectional"))
      (node (ref "Q82") (pin "2") (pinfunction "S_2") (pintype "bidirectional"))
      (node (ref "Q83") (pin "2") (pinfunction "S_2") (pintype "bidirectional"))
      (node (ref "Q84") (pin "2") (pinfunction "S_2") (pintype "bidirectional"))
      (node (ref "Q85") (pin "2") (pinfunction "S_2") (pintype "bidirectional"))
      (node (ref "Q86") (pin "2") (pinfunction "S_2") (pintype "bidirectional"))
      (node (ref "Q87") (pin "2") (pinfunction "S_2") (pintype "bidirectional"))
      (node (ref "Q88") (pin "2") (pinfunction "S_2") (pintype "bidirectional"))
      (node (ref "Q89") (pin "2") (pinfunction "S_2") (pintype "bidirectional"))
      (node (ref "Q9") (pin "2") (pinfunction "S_2") (pintype "bidirectional"))
      (node (ref "Q90") (pin "2") (pinfunction "S_2") (pintype "bidirectional"))
      (node (ref "Q91") (pin "2") (pinfunction "S_2") (pintype "bidirectional"))
      (node (ref "Q92") (pin "2") (pinfunction "S_2") (pintype "bidirectional"))
      (node (ref "Q93") (pin "2") (pinfunction "S_2") (pintype "bidirectional"))
      (node (ref "Q94") (pin "2") (pinfunction "S_2") (pintype "bidirectional"))
      (node (ref "Q95") (pin "2") (pinfunction "S_2") (pintype "bidirectional"))
      (node (ref "Q96") (pin "2") (pinfunction "S_2") (pintype "bidirectional"))
      (node (ref "Q97") (pin "2") (pinfunction "S_2") (pintype "bidirectional"))
      (node (ref "Q98") (pin "2") (pinfunction "S_2") (pintype "bidirectional"))
      (node (ref "Q99") (pin "2") (pinfunction "S_2") (pintype "bidirectional"))
    )
    (net (code "66") (name "LEDPWR") (class "Default")
      (node (ref "J1") (pin "18") (pinfunction "18_18") (pintype "passive"))
    )
    (net (code "67") (name "N$16") (class "Default")
      (node (ref "J1") (pin "16") (pinfunction "16_16") (pintype "passive"))
    )
    (net (code "68") (name "N$17") (class "Default")
      (node (ref "J1") (pin "17") (pinfunction "17_17") (pintype "passive"))
    )
    (net (code "69") (name "Net-(Q13-D)") (class "Default")
      (node (ref "Q13") (pin "3") (pinfunction "D_3") (pintype "bidirectional"))
      (node (ref "Q14") (pin "3") (pinfunction "D_3") (pintype "bidirectional"))
      (node (ref "Q18") (pin "1") (pinfunction "G_1") (pintype "bidirectional"))
      (node (ref "R7") (pin "1") (pinfunction "1_1") (pintype "passive"))
    )
    (net (code "70") (name "Net-(Q15-D)") (class "Default")
      (node (ref "Q15") (pin "3") (pinfunction "D_3") (pintype "bidirectional"))
      (node (ref "Q28") (pin "1") (pinfunction "G_1") (pintype "bidirectional"))
      (node (ref "Q8") (pin "3") (pinfunction "D_3") (pintype "bidirectional"))
      (node (ref "R11") (pin "1") (pinfunction "1_1") (pintype "passive"))
    )
    (net (code "71") (name "Net-(Q15-G)") (class "Default")
      (node (ref "Q15") (pin "1") (pinfunction "G_1") (pintype "bidirectional"))
      (node (ref "Q4") (pin "3") (pinfunction "D_3") (pintype "bidirectional"))
      (node (ref "R4") (pin "1") (pinfunction "1_1") (pintype "passive"))
    )
    (net (code "72") (name "Net-(Q16-D)") (class "Default")
      (node (ref "Q16") (pin "3") (pinfunction "D_3") (pintype "bidirectional"))
      (node (ref "Q23") (pin "3") (pinfunction "D_3") (pintype "bidirectional"))
      (node (ref "Q24") (pin "1") (pinfunction "G_1") (pintype "bidirectional"))
      (node (ref "R12") (pin "1") (pinfunction "1_1") (pintype "passive"))
    )
    (net (code "73") (name "Net-(Q38-D)") (class "Default")
      (node (ref "Q38") (pin "3") (pinfunction "D_3") (pintype "bidirectional"))
      (node (ref "Q39") (pin "3") (pinfunction "D_3") (pintype "bidirectional"))
      (node (ref "Q42") (pin "1") (pinfunction "G_1") (pintype "bidirectional"))
      (node (ref "R19") (pin "1") (pinfunction "1_1") (pintype "passive"))
    )
    (net (code "74") (name "Net-(Q60-D)") (class "Default")
      (node (ref "Q60") (pin "3") (pinfunction "D_3") (pintype "bidirectional"))
      (node (ref "Q61") (pin "3") (pinfunction "D_3") (pintype "bidirectional"))
      (node (ref "Q66") (pin "1") (pinfunction "G_1") (pintype "bidirectional"))
      (node (ref "R29") (pin "1") (pinfunction "1_1") (pintype "passive"))
    )
    (net (code "75") (name "Net-(Q63-D)") (class "Default")
      (node (ref "Q63") (pin "3") (pinfunction "D_3") (pintype "bidirectional"))
      (node (ref "Q68") (pin "1") (pinfunction "G_1") (pintype "bidirectional"))
      (node (ref "R36") (pin "1") (pinfunction "1_1") (pintype "passive"))
    )
    (net (code "76") (name "Net-(Q145-D)") (class "Default")
      (node (ref "Q145") (pin "3") (pinfunction "D_3") (pintype "bidirectional"))
      (node (ref "Q146") (pin "3") (pinfunction "D_3") (pintype "bidirectional"))
      (node (ref "Q155") (pin "1") (pinfunction "G_1") (pintype "bidirectional"))
      (node (ref "R75") (pin "1") (pinfunction "1_1") (pintype "passive"))
    )
    (net (code "77") (name "Net-(Q148-D)") (class "Default")
      (node (ref "Q148") (pin "3") (pinfunction "D_3") (pintype "bidirectional"))
      (node (ref "Q149") (pin "1") (pinfunction "G_1") (pintype "bidirectional"))
      (node (ref "Q72") (pin "3") (pinfunction "D_3") (pintype "bidirectional"))
      (node (ref "R77") (pin "1") (pinfunction "1_1") (pintype "passive"))
    )
    (net (code "78") (name "Net-(Q150-G)") (class "Default")
      (node (ref "Q150") (pin "1") (pinfunction "G_1") (pintype "bidirectional"))
      (node (ref "Q64") (pin "3") (pinfunction "D_3") (pintype "bidirectional"))
      (node (ref "Q68") (pin "3") (pinfunction "D_3") (pintype "bidirectional"))
      (node (ref "R76") (pin "1") (pinfunction "1_1") (pintype "passive"))
    )
    (net (code "79") (name "Net-(Q163-D)") (class "Default")
      (node (ref "Q163") (pin "3") (pinfunction "D_3") (pintype "bidirectional"))
      (node (ref "Q165") (pin "1") (pinfunction "G_1") (pintype "bidirectional"))
      (node (ref "R86") (pin "1") (pinfunction "1_1") (pintype "passive"))
    )
    (net (code "80") (name "Net-(Q164-D)") (class "Default")
      (node (ref "Q164") (pin "3") (pinfunction "D_3") (pintype "bidirectional"))
      (node (ref "Q165") (pin "3") (pinfunction "D_3") (pintype "bidirectional"))
      (node (ref "Q169") (pin "1") (pinfunction "G_1") (pintype "bidirectional"))
      (node (ref "R87") (pin "1") (pinfunction "1_1") (pintype "passive"))
    )
    (net (code "81") (name "Net-(Q166-D)") (class "Default")
      (node (ref "Q166") (pin "3") (pinfunction "D_3") (pintype "bidirectional"))
      (node (ref "Q167") (pin "3") (pinfunction "D_3") (pintype "bidirectional"))
      (node (ref "Q168") (pin "1") (pinfunction "G_1") (pintype "bidirectional"))
      (node (ref "R88") (pin "1") (pinfunction "1_1") (pintype "passive"))
    )
    (net (code "82") (name "Net-(Q177-D)") (class "Default")
      (node (ref "Q177") (pin "3") (pinfunction "D_3") (pintype "bidirectional"))
      (node (ref "Q179") (pin "1") (pinfunction "G_1") (pintype "bidirectional"))
      (node (ref "R94") (pin "1") (pinfunction "1_1") (pintype "passive"))
    )
    (net (code "83") (name "Net-(Q178-D)") (class "Default")
      (node (ref "Q178") (pin "3") (pinfunction "D_3") (pintype "bidirectional"))
      (node (ref "Q179") (pin "3") (pinfunction "D_3") (pintype "bidirectional"))
      (node (ref "Q183") (pin "1") (pinfunction "G_1") (pintype "bidirectional"))
      (node (ref "R95") (pin "1") (pinfunction "1_1") (pintype "passive"))
    )
    (net (code "84") (name "Net-(Q180-D)") (class "Default")
      (node (ref "Q180") (pin "3") (pinfunction "D_3") (pintype "bidirectional"))
      (node (ref "Q181") (pin "3") (pinfunction "D_3") (pintype "bidirectional"))
      (node (ref "Q182") (pin "1") (pinfunction "G_1") (pintype "bidirectional"))
      (node (ref "R96") (pin "1") (pinfunction "1_1") (pintype "passive"))
    )
    (net (code "85") (name "OP") (class "Default")
      (node (ref "J1") (pin "15") (pinfunction "15_15") (pintype "passive"))
      (node (ref "Q105") (pin "1") (pinfunction "G_1") (pintype "bidirectional"))
      (node (ref "Q164") (pin "1") (pinfunction "G_1") (pintype "bidirectional"))
      (node (ref "Q178") (pin "1") (pinfunction "G_1") (pintype "bidirectional"))
      (node (ref "Q64") (pin "1") (pinfunction "G_1") (pintype "bidirectional"))
      (node (ref "Q8") (pin "1") (pinfunction "G_1") (pintype "bidirectional"))
    )
    (net (code "86") (name "SUM0") (class "Default")
      (node (ref "J1") (pin "10") (pinfunction "10_10") (pintype "passive"))
      (node (ref "Q127") (pin "3") (pinfunction "D_3") (pintype "bidirectional"))
      (node (ref "R65") (pin "1") (pinfunction "1_1") (pintype "passive"))
    )
    (net (code "87") (name "SUM0'") (class "Default")
      (node (ref "Q127") (pin "1") (pinfunction "G_1") (pintype "bidirectional"))
      (node (ref "Q147") (pin "3") (pinfunction "D_3") (pintype "bidirectional"))
      (node (ref "Q155") (pin "3") (pinfunction "D_3") (pintype "bidirectional"))
      (node (ref "Q84") (pin "1") (pinfunction "G_1") (pintype "bidirectional"))
      (node (ref "Q88") (pin "1") (pinfunction "G_1") (pintype "bidirectional"))
      (node (ref "R80") (pin "1") (pinfunction "1_1") (pintype "passive"))
    )
    (net (code "88") (name "SUM1") (class "Default")
      (node (ref "J1") (pin "11") (pinfunction "11_11") (pintype "passive"))
      (node (ref "Q85") (pin "3") (pinfunction "D_3") (pintype "bidirectional"))
      (node (ref "Q86") (pin "3") (pinfunction "D_3") (pintype "bidirectional"))
      (node (ref "R43") (pin "1") (pinfunction "1_1") (pintype "passive"))
    )
    (net (code "89") (name "SUM1'") (class "Default")
      (node (ref "Q17") (pin "3") (pinfunction "D_3") (pintype "bidirectional"))
      (node (ref "Q18") (pin "3") (pinfunction "D_3") (pintype "bidirectional"))
      (node (ref "Q73") (pin "1") (pinfunction "G_1") (pintype "bidirectional"))
      (node (ref "Q75") (pin "1") (pinfunction "G_1") (pintype "bidirectional"))
      (node (ref "R8") (pin "1") (pinfunction "1_1") (pintype "passive"))
    )
    (net (code "90") (name "SUM2") (class "Default")
      (node (ref "J1") (pin "12") (pinfunction "12_12") (pintype "passive"))
      (node (ref "Q103") (pin "3") (pinfunction "D_3") (pintype "bidirectional"))
      (node (ref "Q104") (pin "3") (pinfunction "D_3") (pintype "bidirectional"))
      (node (ref "R52") (pin "1") (pinfunction "1_1") (pintype "passive"))
    )
    (net (code "91") (name "SUM2'") (class "Default")
      (node (ref "Q41") (pin "3") (pinfunction "D_3") (pintype "bidirectional"))
      (node (ref "Q42") (pin "3") (pinfunction "D_3") (pintype "bidirectional"))
      (node (ref "Q91") (pin "1") (pinfunction "G_1") (pintype "bidirectional"))
      (node (ref "Q93") (pin "1") (pinfunction "G_1") (pintype "bidirectional"))
      (node (ref "R21") (pin "1") (pinfunction "1_1") (pintype "passive"))
    )
    (net (code "92") (name "SUM3") (class "Default")
      (node (ref "J1") (pin "13") (pinfunction "13_13") (pintype "passive"))
      (node (ref "Q123") (pin "3") (pinfunction "D_3") (pintype "bidirectional"))
      (node (ref "Q124") (pin "3") (pinfunction "D_3") (pintype "bidirectional"))
      (node (ref "R62") (pin "1") (pinfunction "1_1") (pintype "passive"))
    )
    (net (code "93") (name "SUM3'") (class "Default")
      (node (ref "Q110") (pin "1") (pinfunction "G_1") (pintype "bidirectional"))
      (node (ref "Q112") (pin "1") (pinfunction "G_1") (pintype "bidirectional"))
      (node (ref "Q65") (pin "3") (pinfunction "D_3") (pintype "bidirectional"))
      (node (ref "Q66") (pin "3") (pinfunction "D_3") (pintype "bidirectional"))
      (node (ref "R33") (pin "1") (pinfunction "1_1") (pintype "passive"))
    )
    (net (code "94") (name "VCC") (class "Default")
      (node (ref "C14") (pin "1") (pinfunction "1_1") (pintype "passive"))
      (node (ref "J1") (pin "19") (pinfunction "19_19") (pintype "passive"))
      (node (ref "R1") (pin "2") (pinfunction "2_2") (pintype "passive"))
      (node (ref "R10") (pin "2") (pinfunction "2_2") (pintype "passive"))
      (node (ref "R11") (pin "2") (pinfunction "2_2") (pintype "passive"))
      (node (ref "R12") (pin "2") (pinfunction "2_2") (pintype "passive"))
      (node (ref "R13") (pin "2") (pinfunction "2_2") (pintype "passive"))
      (node (ref "R14") (pin "2") (pinfunction "2_2") (pintype "passive"))
      (node (ref "R15") (pin "2") (pinfunction "2_2") (pintype "passive"))
      (node (ref "R16") (pin "2") (pinfunction "2_2") (pintype "passive"))
      (node (ref "R17") (pin "2") (pinfunction "2_2") (pintype "passive"))
      (node (ref "R18") (pin "2") (pinfunction "2_2") (pintype "passive"))
      (node (ref "R19") (pin "2") (pinfunction "2_2") (pintype "passive"))
      (node (ref "R2") (pin "2") (pinfunction "2_2") (pintype "passive"))
      (node (ref "R21") (pin "2") (pinfunction "2_2") (pintype "passive"))
      (node (ref "R22") (pin "2") (pinfunction "2_2") (pintype "passive"))
      (node (ref "R23") (pin "2") (pinfunction "2_2") (pintype "passive"))
      (node (ref "R24") (pin "2") (pinfunction "2_2") (pintype "passive"))
      (node (ref "R25") (pin "2") (pinfunction "2_2") (pintype "passive"))
      (node (ref "R26") (pin "2") (pinfunction "2_2") (pintype "passive"))
      (node (ref "R27") (pin "2") (pinfunction "2_2") (pintype "passive"))
      (node (ref "R28") (pin "2") (pinfunction "2_2") (pintype "passive"))
      (node (ref "R29") (pin "2") (pinfunction "2_2") (pintype "passive"))
      (node (ref "R3") (pin "2") (pinfunction "2_2") (pintype "passive"))
      (node (ref "R33") (pin "2") (pinfunction "2_2") (pintype "passive"))
      (node (ref "R34") (pin "2") (pinfunction "2_2") (pintype "passive"))
      (node (ref "R35") (pin "2") (pinfunction "2_2") (pintype "passive"))
      (node (ref "R36") (pin "2") (pinfunction "2_2") (pintype "passive"))
      (node (ref "R37") (pin "2") (pinfunction "2_2") (pintype "passive"))
      (node (ref "R38") (pin "2") (pinfunction "2_2") (pintype "passive"))
      (node (ref "R39") (pin "2") (pinfunction "2_2") (pintype "passive"))
      (node (ref "R4") (pin "2") (pinfunction "2_2") (pintype "passive"))
      (node (ref "R40") (pin "2") (pinfunction "2_2") (pintype "passive"))
      (node (ref "R41") (pin "2") (pinfunction "2_2") (pintype "passive"))
      (node (ref "R42") (pin "2") (pinfunction "2_2") (pintype "passive"))
      (node (ref "R43") (pin "2") (pinfunction "2_2") (pintype "passive"))
      (node (ref "R44") (pin "2") (pinfunction "2_2") (pintype "passive"))
      (node (ref "R45") (pin "2") (pinfunction "2_2") (pintype "passive"))
      (node (ref "R46") (pin "2") (pinfunction "2_2") (pintype "passive"))
      (node (ref "R47") (pin "2") (pinfunction "2_2") (pintype "passive"))
      (node (ref "R48") (pin "2") (pinfunction "2_2") (pintype "passive"))
      (node (ref "R49") (pin "2") (pinfunction "2_2") (pintype "passive"))
      (node (ref "R5") (pin "2") (pinfunction "2_2") (pintype "passive"))
      (node (ref "R50") (pin "2") (pinfunction "2_2") (pintype "passive"))
      (node (ref "R51") (pin "2") (pinfunction "2_2") (pintype "passive"))
      (node (ref "R52") (pin "2") (pinfunction "2_2") (pintype "passive"))
      (node (ref "R53") (pin "2") (pinfunction "2_2") (pintype "passive"))
      (node (ref "R54") (pin "2") (pinfunction "2_2") (pintype "passive"))
      (node (ref "R55") (pin "2") (pinfunction "2_2") (pintype "passive"))
      (node (ref "R56") (pin "2") (pinfunction "2_2") (pintype "passive"))
      (node (ref "R57") (pin "2") (pinfunction "2_2") (pintype "passive"))
      (node (ref "R58") (pin "2") (pinfunction "2_2") (pintype "passive"))
      (node (ref "R59") (pin "2") (pinfunction "2_2") (pintype "passive"))
      (node (ref "R6") (pin "2") (pinfunction "2_2") (pintype "passive"))
      (node (ref "R60") (pin "2") (pinfunction "2_2") (pintype "passive"))
      (node (ref "R61") (pin "2") (pinfunction "2_2") (pintype "passive"))
      (node (ref "R62") (pin "2") (pinfunction "2_2") (pintype "passive"))
      (node (ref "R63") (pin "2") (pinfunction "2_2") (pintype "passive"))
      (node (ref "R64") (pin "2") (pinfunction "2_2") (pintype "passive"))
      (node (ref "R65") (pin "2") (pinfunction "2_2") (pintype "passive"))
      (node (ref "R66") (pin "2") (pinfunction "2_2") (pintype "passive"))
      (node (ref "R67") (pin "2") (pinfunction "2_2") (pintype "passive"))
      (node (ref "R7") (pin "2") (pinfunction "2_2") (pintype "passive"))
      (node (ref "R72") (pin "2") (pinfunction "2_2") (pintype "passive"))
      (node (ref "R73") (pin "2") (pinfunction "2_2") (pintype "passive"))
      (node (ref "R74") (pin "2") (pinfunction "2_2") (pintype "passive"))
      (node (ref "R75") (pin "2") (pinfunction "2_2") (pintype "passive"))
      (node (ref "R76") (pin "2") (pinfunction "2_2") (pintype "passive"))
      (node (ref "R77") (pin "2") (pinfunction "2_2") (pintype "passive"))
      (node (ref "R78") (pin "2") (pinfunction "2_2") (pintype "passive"))
      (node (ref "R8") (pin "2") (pinfunction "2_2") (pintype "passive"))
      (node (ref "R80") (pin "2") (pinfunction "2_2") (pintype "passive"))
      (node (ref "R81") (pin "2") (pinfunction "2_2") (pintype "passive"))
      (node (ref "R82") (pin "2") (pinfunction "2_2") (pintype "passive"))
      (node (ref "R86") (pin "2") (pinfunction "2_2") (pintype "passive"))
      (node (ref "R87") (pin "2") (pinfunction "2_2") (pintype "passive"))
      (node (ref "R88") (pin "2") (pinfunction "2_2") (pintype "passive"))
      (node (ref "R89") (pin "2") (pinfunction "2_2") (pintype "passive"))
      (node (ref "R9") (pin "2") (pinfunction "2_2") (pintype "passive"))
      (node (ref "R94") (pin "2") (pinfunction "2_2") (pintype "passive"))
      (node (ref "R95") (pin "2") (pinfunction "2_2") (pintype "passive"))
      (node (ref "R96") (pin "2") (pinfunction "2_2") (pintype "passive"))
      (node (ref "R97") (pin "2") (pinfunction "2_2") (pintype "passive"))
    )
    (net (code "95") (name "{slash}CRYOUT") (class "Default")
      (node (ref "Q111") (pin "1") (pinfunction "G_1") (pintype "bidirectional"))
      (node (ref "Q114") (pin "3") (pinfunction "D_3") (pintype "bidirectional"))
      (node (ref "Q116") (pin "1") (pinfunction "G_1") (pintype "bidirectional"))
      (node (ref "Q92") (pin "1") (pinfunction "G_1") (pintype "bidirectional"))
      (node (ref "Q96") (pin "1") (pinfunction "G_1") (pintype "bidirectional"))
      (node (ref "R64") (pin "1") (pinfunction "1_1") (pintype "passive"))
    )
    (net (code "96") (name "{slash}OP") (class "Default")
      (node (ref "Q105") (pin "3") (pinfunction "D_3") (pintype "bidirectional"))
      (node (ref "Q16") (pin "1") (pinfunction "G_1") (pintype "bidirectional"))
      (node (ref "Q166") (pin "1") (pinfunction "G_1") (pintype "bidirectional"))
      (node (ref "Q180") (pin "1") (pinfunction "G_1") (pintype "bidirectional"))
      (node (ref "Q72") (pin "1") (pinfunction "G_1") (pintype "bidirectional"))
      (node (ref "R54") (pin "1") (pinfunction "1_1") (pintype "passive"))
    )
  )
)
